# untitled.net
KiCad netlist of a schematic drawn in EAGLE
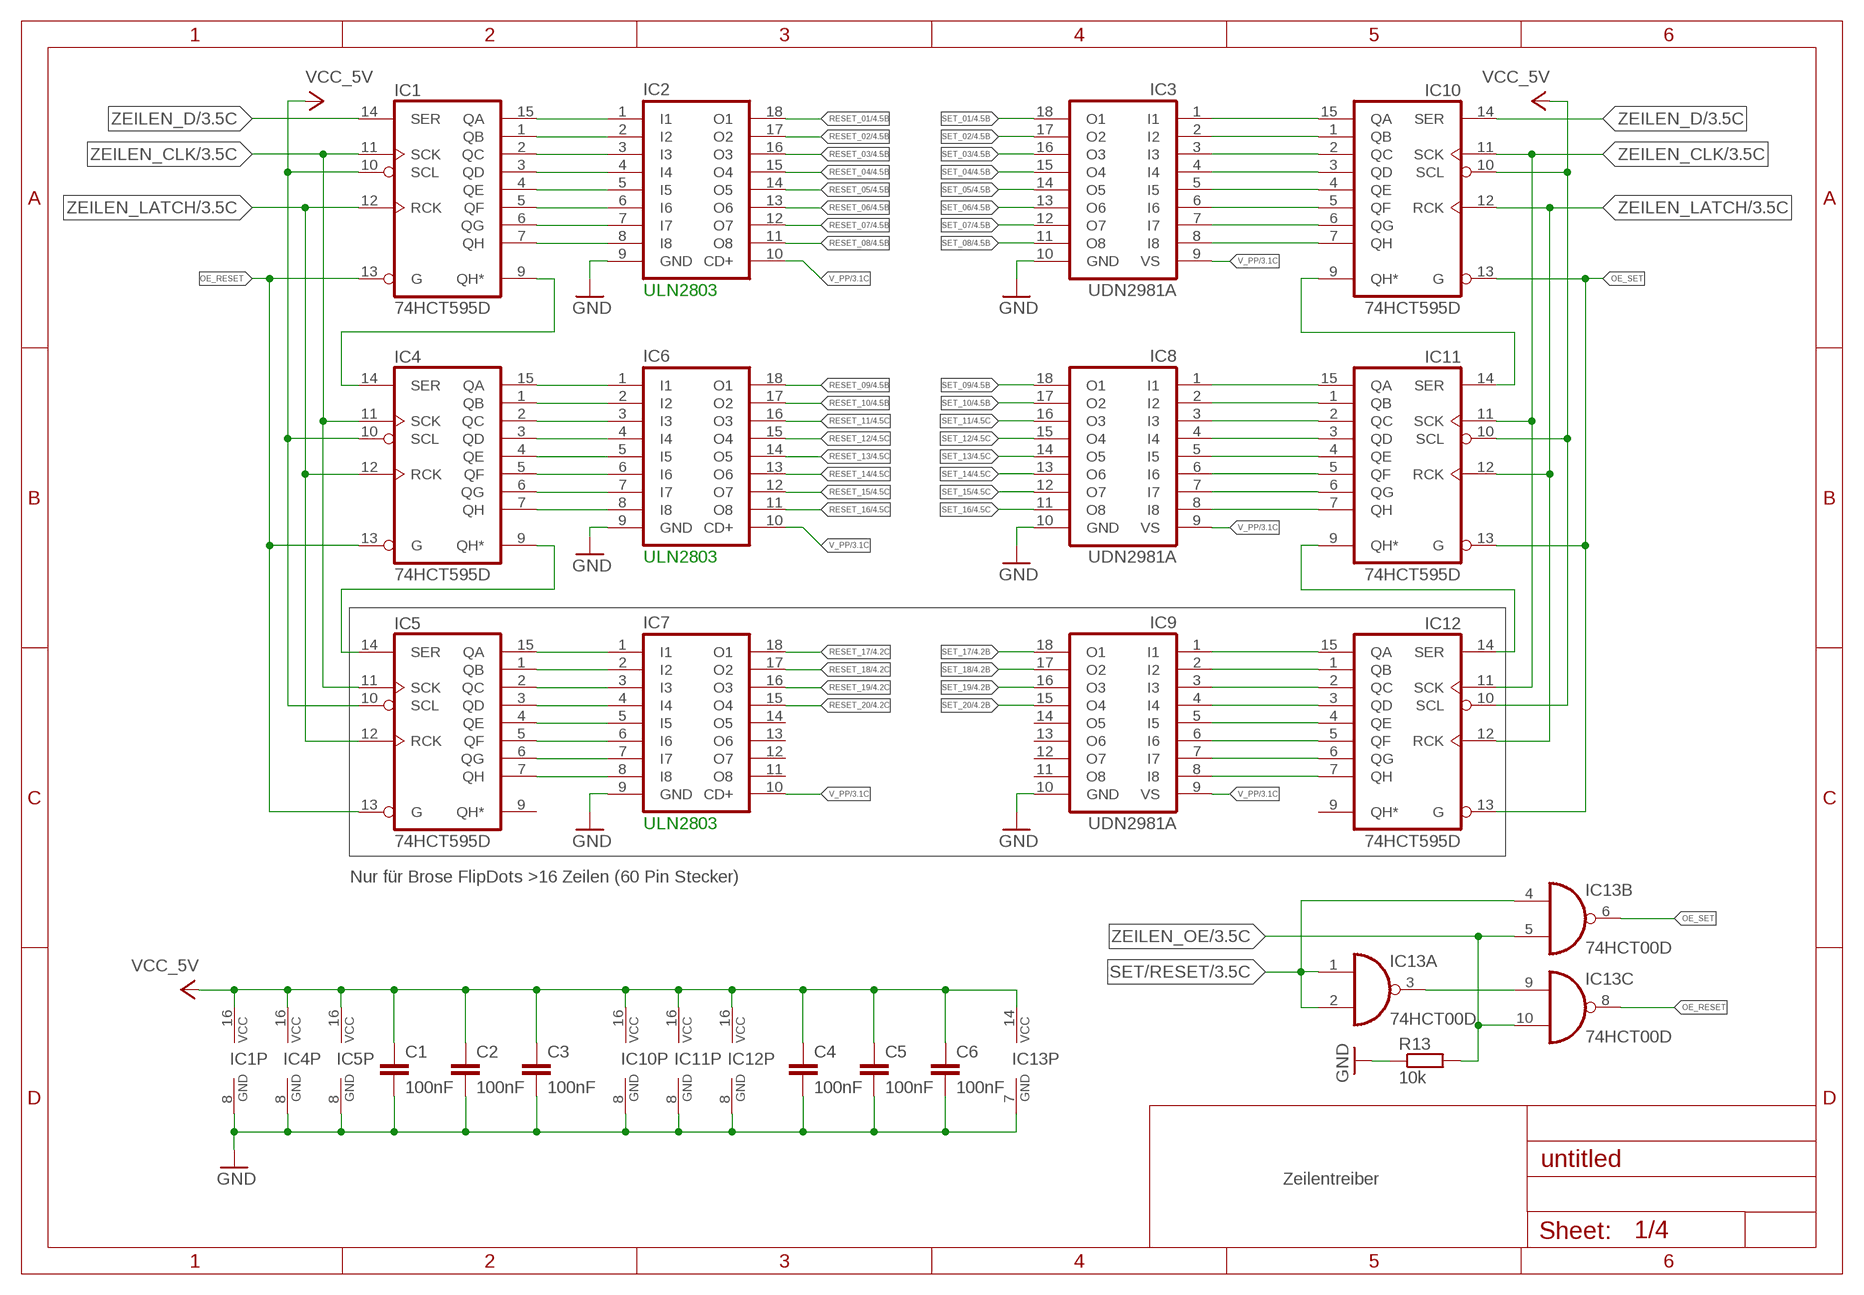
[diagram p0: schematic, sheet 1]
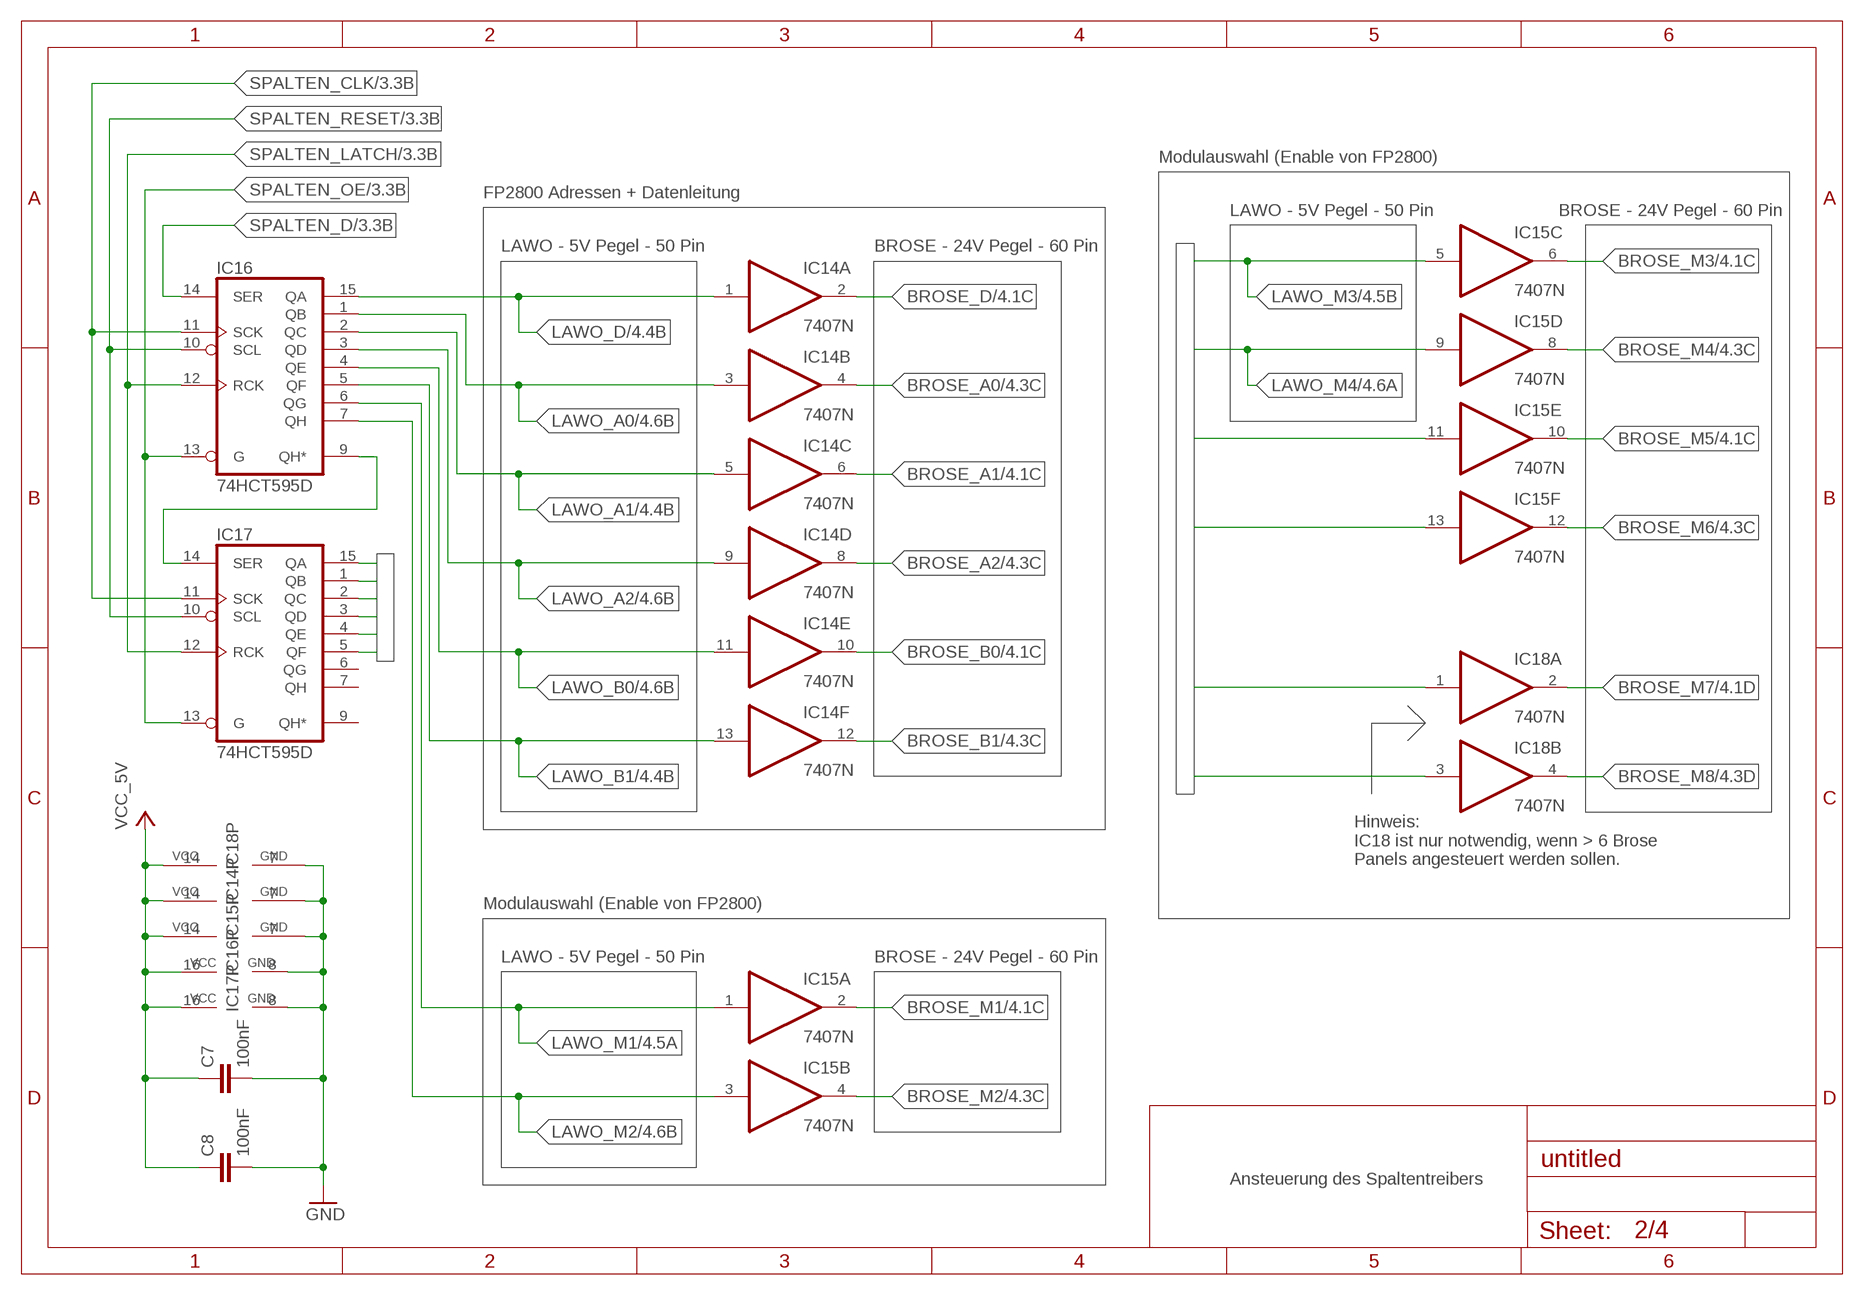
[diagram p1: schematic, sheet 2]
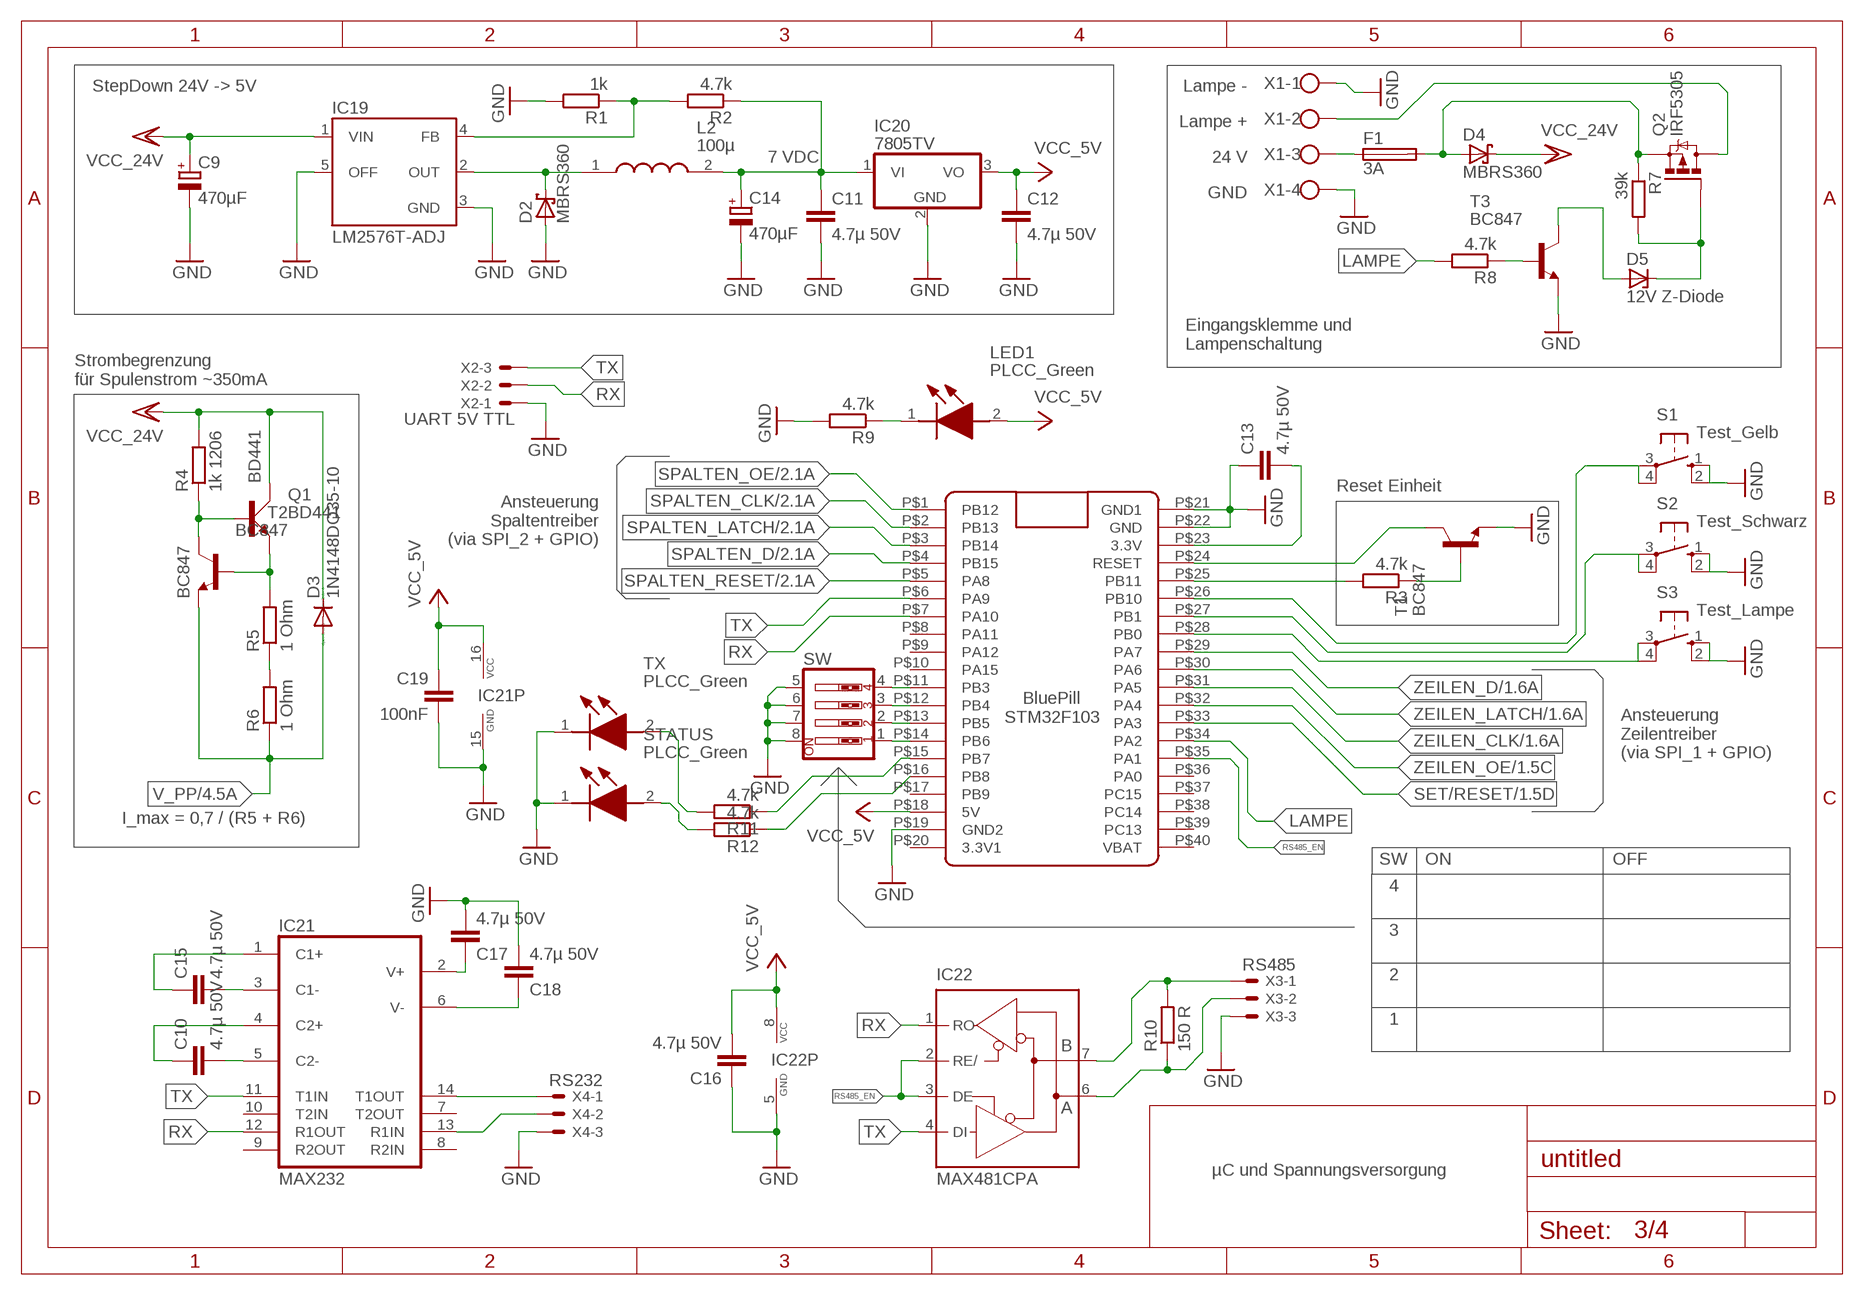
[diagram p2: schematic, sheet 3]
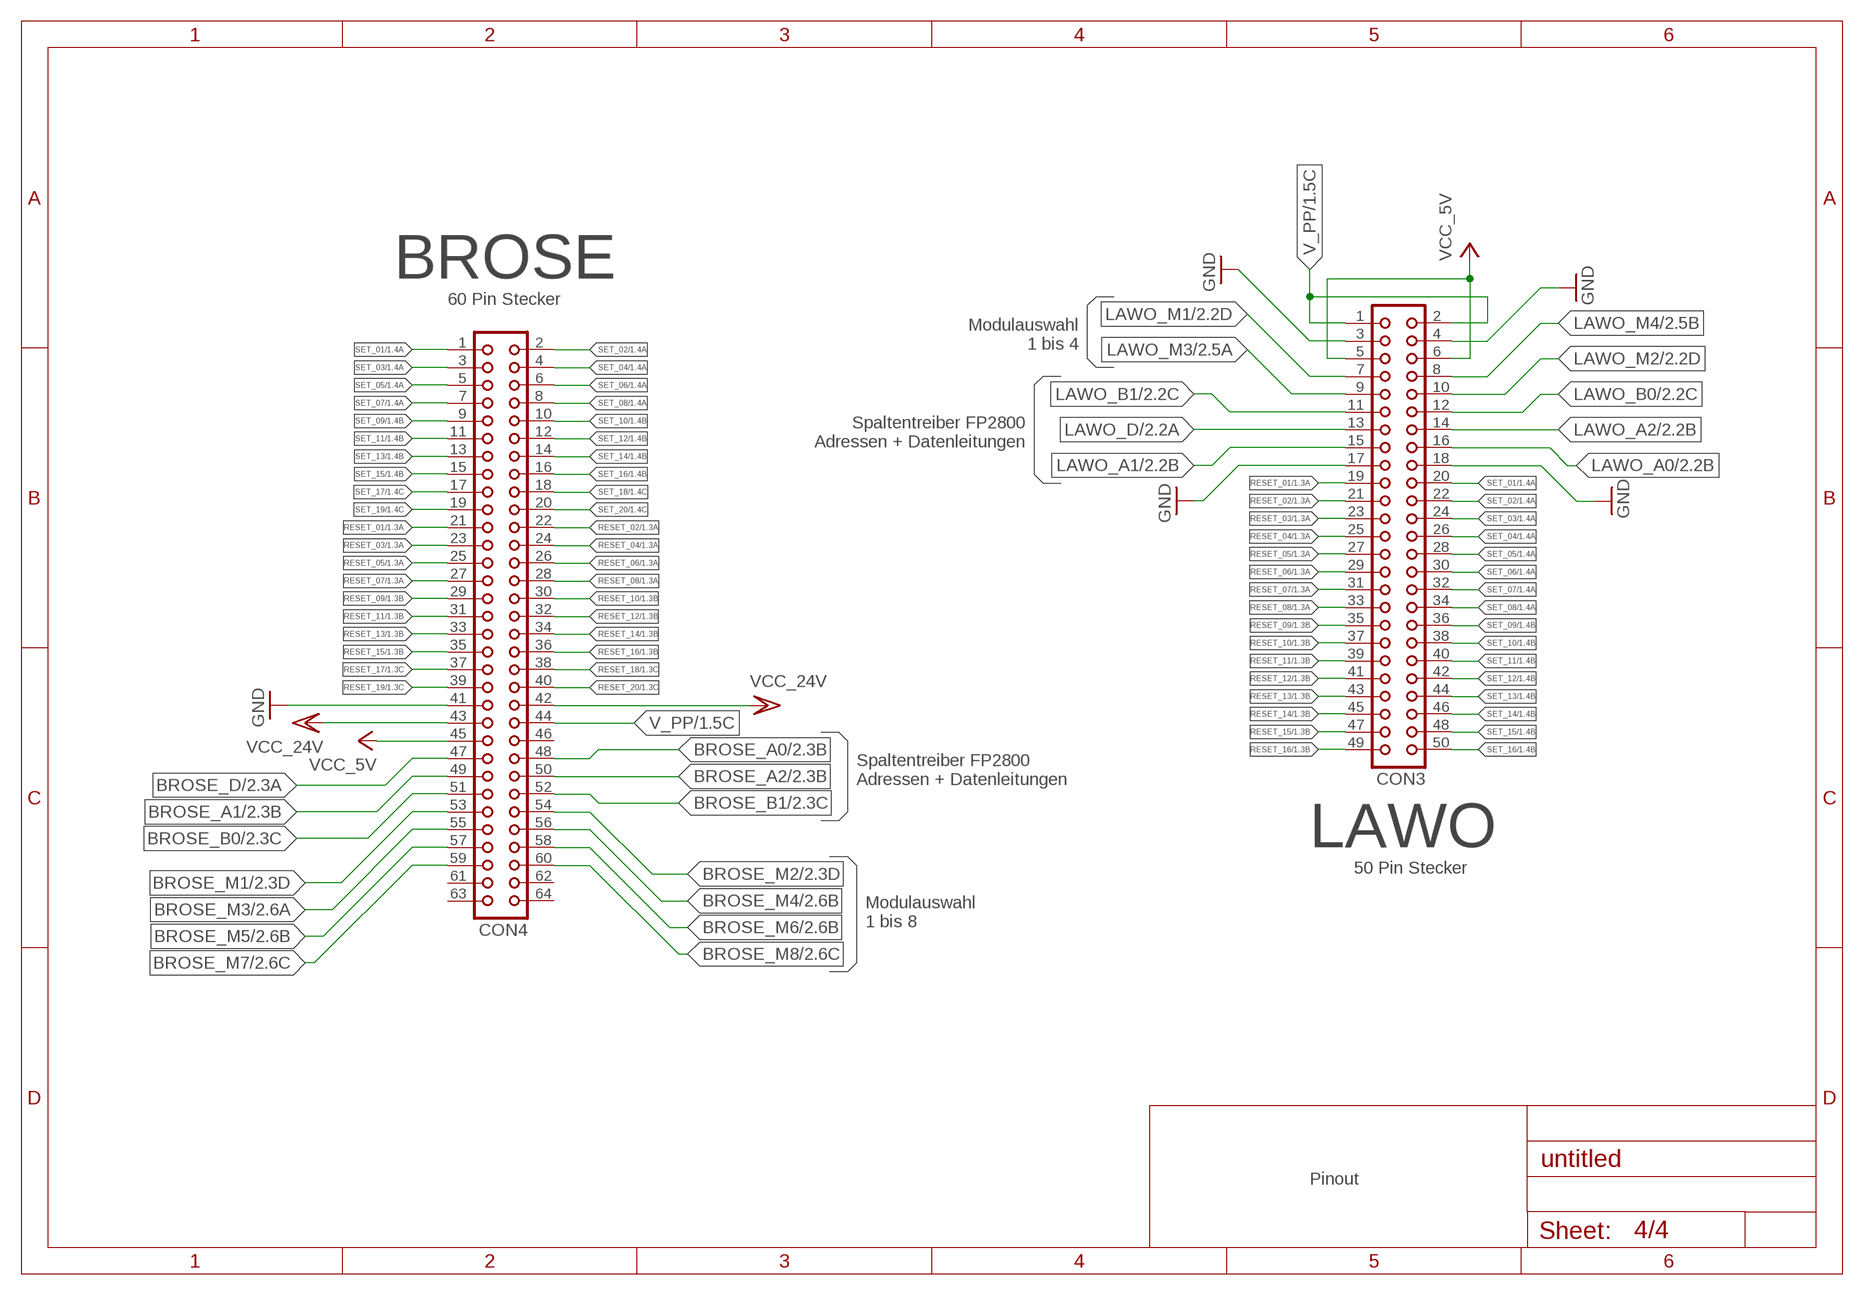
[diagram p3: schematic, sheet 4]

(export (version "E")
  (design (tool "Eeschema 10.0.6"))
  (components
    (comp (ref "C9")
      (value "470µF")
      (footprint "eagle-import:E5-10,5")
      (libsource (lib "eagle-import") (part "CPOL-EUE5-10.5"))
    )
    (comp (ref "C10")
      (value "4.7µ 50V")
      (footprint "eagle-import:C1210K")
      (libsource (lib "eagle-import") (part "C-EUC1210K"))
    )
    (comp (ref "C11")
      (value "4.7µ 50V")
      (footprint "eagle-import:C1210K")
      (libsource (lib "eagle-import") (part "C-EUC1210K"))
    )
    (comp (ref "C12")
      (value "4.7µ 50V")
      (footprint "eagle-import:C1210K")
      (libsource (lib "eagle-import") (part "C-EUC1210K"))
    )
    (comp (ref "C13")
      (value "4.7µ 50V")
      (footprint "eagle-import:C1210K")
      (libsource (lib "eagle-import") (part "C-EUC1210K"))
    )
    (comp (ref "C14")
      (value "470µF")
      (footprint "eagle-import:E5-10,5")
      (libsource (lib "eagle-import") (part "CPOL-EUE5-10.5"))
    )
    (comp (ref "C15")
      (value "4.7µ 50V")
      (footprint "eagle-import:C1210K")
      (libsource (lib "eagle-import") (part "C-EUC1210K"))
    )
    (comp (ref "C16")
      (value "4.7µ 50V")
      (footprint "eagle-import:C1210K")
      (libsource (lib "eagle-import") (part "C-EUC1210K"))
    )
    (comp (ref "C17")
      (value "4.7µ 50V")
      (footprint "eagle-import:C1210K")
      (libsource (lib "eagle-import") (part "C-EUC1210K"))
    )
    (comp (ref "C18")
      (value "4.7µ 50V")
      (footprint "eagle-import:C1210K")
      (libsource (lib "eagle-import") (part "C-EUC1210K"))
    )
    (comp (ref "C19")
      (value "100nF")
      (footprint "eagle-import:C1206K")
      (libsource (lib "eagle-import") (part "C-EUC1206K"))
    )
    (comp (ref "D2")
      (value "MBRS360")
      (footprint "eagle-import:SMC")
      (libsource (lib "eagle-import") (part "MBRS30T34"))
    )
    (comp (ref "D3")
      (value "1N4148DO35-10")
      (footprint "eagle-import:DO35-10")
      (libsource (lib "eagle-import") (part "1N4148DO35-10"))
    )
    (comp (ref "D4")
      (value "MBRS360")
      (footprint "eagle-import:SMC")
      (libsource (lib "eagle-import") (part "MBRS30T34"))
    )
    (comp (ref "D5")
      (value "12V Z-Diode")
      (footprint "eagle-import:SOD80C")
      (libsource (lib "eagle-import") (part "ZENER-DIODESOD80C"))
    )
    (comp (ref "F1")
      (value "3A")
      (footprint "eagle-import:SH22,5")
      (fields (field (name "MF") "SCHURTER") (field (name "MPN") "0031.8201"))
      (libsource (lib "eagle-import") (part "SH22,5"))
    )
    (comp (ref "IC19")
      (value "LM2576T-ADJ")
      (footprint "eagle-import:TO220-5")
      (libsource (lib "eagle-import") (part "LM2576T"))
    )
    (comp (ref "IC20")
      (value "7805TV")
      (footprint "eagle-import:TO220V")
      (libsource (lib "eagle-import") (part "78TV05"))
    )
    (comp (ref "IC21")
      (value "MAX232")
      (footprint "eagle-import:DIL16")
      (fields (field (name "MF") "MAXIM") (field (name "MPN") "MAX232ACPE+"))
      (libsource (lib "eagle-import") (part "MAX232"))
    )
    (comp (ref "IC22")
      (value "MAX481CPA")
      (footprint "eagle-import:DIL08")
      (fields (field (name "MPN") "MAX481CPA+"))
      (libsource (lib "eagle-import") (part "MAX481CPA"))
    )
    (comp (ref "L2")
      (value "100µ")
      (footprint "eagle-import:09HCP121M50")
      (fields
        (field (name "MANUFACTURER_PART_NUMBER") "09HCP-121M-50")
        (field (name "MOUSER_PART_NUMBER") "434-09HCP-121M")
      )
      (libsource (lib "eagle-import") (part "09HCP-121M-50"))
    )
    (comp (ref "LED1")
      (value "PLCC_Green")
      (footprint "eagle-import:LEDM3528X190N")
      (fields
        (field (name "MANUFACTURER_PART_NUMBER") "LTST-T680TGWT")
        (field (name "MOUSER_PART_NUMBER") "859-LTST-T680TGWT")
      )
      (libsource (lib "eagle-import") (part "LTST-T680TGWT"))
    )
    (comp (ref "Q1")
      (value "BD441")
      (footprint "eagle-import:TO126AV")
      (libsource (lib "eagle-import") (part "BD437"))
    )
    (comp (ref "Q2")
      (value "IRF5305")
      (footprint "eagle-import:TO220BV")
      (libsource (lib "eagle-import") (part "IRF9530"))
    )
    (comp (ref "R1")
      (value "1k")
      (footprint "eagle-import:R0805")
      (libsource (lib "eagle-import") (part "R-EU_R0805"))
    )
    (comp (ref "R2")
      (value "4.7k")
      (footprint "eagle-import:R0805")
      (libsource (lib "eagle-import") (part "R-EU_R0805"))
    )
    (comp (ref "R3")
      (value "4.7k")
      (footprint "eagle-import:R0805")
      (libsource (lib "eagle-import") (part "R-EU_R0805"))
    )
    (comp (ref "R4")
      (value "1k 1206")
      (footprint "eagle-import:R1206")
      (libsource (lib "eagle-import") (part "R-EU_R1206"))
    )
    (comp (ref "R5")
      (value "1 Ohm")
      (footprint "eagle-import:M1206")
      (libsource (lib "eagle-import") (part "R-EU_M1206"))
    )
    (comp (ref "R6")
      (value "1 Ohm")
      (footprint "eagle-import:M1206")
      (libsource (lib "eagle-import") (part "R-EU_M1206"))
    )
    (comp (ref "R7")
      (value "39k")
      (footprint "eagle-import:R0805")
      (libsource (lib "eagle-import") (part "R-EU_R0805"))
    )
    (comp (ref "R8")
      (value "4.7k")
      (footprint "eagle-import:R0805")
      (libsource (lib "eagle-import") (part "R-EU_R0805"))
    )
    (comp (ref "R9")
      (value "4.7k")
      (footprint "eagle-import:R0805")
      (libsource (lib "eagle-import") (part "R-EU_R0805"))
    )
    (comp (ref "R10")
      (value "150 R")
      (footprint "eagle-import:R1206")
      (libsource (lib "eagle-import") (part "R-EU_R1206"))
    )
    (comp (ref "R11")
      (value "4.7k")
      (footprint "eagle-import:R0805")
      (libsource (lib "eagle-import") (part "R-EU_R0805"))
    )
    (comp (ref "R12")
      (value "4.7k")
      (footprint "eagle-import:R0805")
      (libsource (lib "eagle-import") (part "R-EU_R0805"))
    )
    (comp (ref "S1")
      (value "Test_Gelb")
      (footprint "eagle-import:B3F-10XX")
      (fields (field (name "MPN") "B3F-1000"))
      (libsource (lib "eagle-import") (part "10-XX"))
    )
    (comp (ref "S2")
      (value "Test_Schwarz")
      (footprint "eagle-import:B3F-10XX")
      (fields (field (name "MPN") "B3F-1000"))
      (libsource (lib "eagle-import") (part "10-XX"))
    )
    (comp (ref "S3")
      (value "Test_Lampe")
      (footprint "eagle-import:B3F-10XX")
      (fields (field (name "MPN") "B3F-1000"))
      (libsource (lib "eagle-import") (part "10-XX"))
    )
    (comp (ref "STATUS")
      (value "PLCC_Green")
      (footprint "eagle-import:LEDM3528X190N")
      (fields
        (field (name "MANUFACTURER_PART_NUMBER") "LTST-T680TGWT")
        (field (name "MOUSER_PART_NUMBER") "859-LTST-T680TGWT")
      )
      (libsource (lib "eagle-import") (part "LTST-T680TGWT"))
    )
    (comp (ref "SW")
      (value "SW_DIP-4")
      (footprint "eagle-import:EDG-04")
      (libsource (lib "eagle-import") (part "SW_DIP-4"))
    )
    (comp (ref "T1")
      (value "BC847")
      (footprint "eagle-import:SOT23")
      (libsource (lib "eagle-import") (part "BC847"))
    )
    (comp (ref "T2")
      (value "BC847")
      (footprint "eagle-import:SOT23")
      (libsource (lib "eagle-import") (part "BC847"))
    )
    (comp (ref "T3")
      (value "BC847")
      (footprint "eagle-import:SOT23")
      (libsource (lib "eagle-import") (part "BC847"))
    )
    (comp (ref "TX")
      (value "PLCC_Green")
      (footprint "eagle-import:LEDM3528X190N")
      (fields
        (field (name "MANUFACTURER_PART_NUMBER") "LTST-T680TGWT")
        (field (name "MOUSER_PART_NUMBER") "859-LTST-T680TGWT")
      )
      (libsource (lib "eagle-import") (part "LTST-T680TGWT"))
    )
    (comp (ref "U$1")
      (value "BLUE_PILL")
      (footprint "eagle-import:BLUE_PILL")
      (libsource (lib "eagle-import") (part "BLUE_PILL"))
    )
    (comp (ref "X1")
      (value "W237-4")
      (footprint "eagle-import:W237-4")
      (libsource (lib "eagle-import") (part "W237-4"))
    )
    (comp (ref "X2")
      (value "UART 5V TTL")
      (footprint "eagle-import:22-23-2031")
      (fields (field (name "MF") "MOLEX") (field (name "MPN") "22-23-2031"))
      (libsource (lib "eagle-import") (part "22-23-2031"))
    )
    (comp (ref "X3")
      (value "RS485")
      (footprint "eagle-import:22-23-2031")
      (fields (field (name "MF") "MOLEX") (field (name "MPN") "22-23-2031"))
      (libsource (lib "eagle-import") (part "22-23-2031"))
    )
    (comp (ref "X4")
      (value "RS232")
      (footprint "eagle-import:22-23-2031")
      (fields (field (name "MF") "MOLEX") (field (name "MPN") "22-23-2031"))
      (libsource (lib "eagle-import") (part "22-23-2031"))
    )
    (comp (ref "CON3")
      (value "CON50")
      (footprint "eagle-import:CON50")
      (libsource (lib "eagle-import") (part "CON50"))
    )
    (comp (ref "CON4")
      (value "CON64")
      (footprint "eagle-import:CON64")
      (libsource (lib "eagle-import") (part "CON64"))
    )
    (comp (ref "C7")
      (value "100nF")
      (footprint "eagle-import:C1206K")
      (libsource (lib "eagle-import") (part "resistor_C-EUC1206K"))
    )
    (comp (ref "C8")
      (value "100nF")
      (footprint "eagle-import:C1206K")
      (libsource (lib "eagle-import") (part "resistor_C-EUC1206K"))
    )
    (comp (ref "IC14")
      (value "7407N")
      (footprint "eagle-import:DIL14")
      (libsource (lib "eagle-import") (part "7407N"))
    )
    (comp (ref "IC15")
      (value "7407N")
      (footprint "eagle-import:DIL14")
      (libsource (lib "eagle-import") (part "7407N"))
    )
    (comp (ref "IC16")
      (value "74HCT595D")
      (footprint "eagle-import:SO16")
      (libsource (lib "eagle-import") (part "74595DHCT"))
    )
    (comp (ref "IC17")
      (value "74HCT595D")
      (footprint "eagle-import:SO16")
      (libsource (lib "eagle-import") (part "74595DHCT"))
    )
    (comp (ref "IC18")
      (value "7407N")
      (footprint "eagle-import:DIL14")
      (libsource (lib "eagle-import") (part "7407N"))
    )
    (comp (ref "C1")
      (value "100nF")
      (footprint "eagle-import:C1206K")
      (libsource (lib "eagle-import") (part "C-EUC1206K"))
    )
    (comp (ref "C2")
      (value "100nF")
      (footprint "eagle-import:C1206K")
      (libsource (lib "eagle-import") (part "C-EUC1206K"))
    )
    (comp (ref "C3")
      (value "100nF")
      (footprint "eagle-import:C1206K")
      (libsource (lib "eagle-import") (part "C-EUC1206K"))
    )
    (comp (ref "C4")
      (value "100nF")
      (footprint "eagle-import:C1206K")
      (libsource (lib "eagle-import") (part "C-EUC1206K"))
    )
    (comp (ref "C5")
      (value "100nF")
      (footprint "eagle-import:C1206K")
      (libsource (lib "eagle-import") (part "C-EUC1206K"))
    )
    (comp (ref "C6")
      (value "100nF")
      (footprint "eagle-import:C1206K")
      (libsource (lib "eagle-import") (part "C-EUC1206K"))
    )
    (comp (ref "IC1")
      (value "74HCT595D")
      (footprint "eagle-import:SO16")
      (libsource (lib "eagle-import") (part "74595DHCT"))
    )
    (comp (ref "IC2")
      (value "ULN2803A")
      (footprint "eagle-import:DIL18")
      (libsource (lib "eagle-import") (part "ULN2803A"))
    )
    (comp (ref "IC3")
      (value "UDN2981A")
      (footprint "eagle-import:DIL18")
      (libsource (lib "eagle-import") (part "UDN298A1"))
    )
    (comp (ref "IC4")
      (value "74HCT595D")
      (footprint "eagle-import:SO16")
      (libsource (lib "eagle-import") (part "74595DHCT"))
    )
    (comp (ref "IC5")
      (value "74HCT595D")
      (footprint "eagle-import:SO16")
      (libsource (lib "eagle-import") (part "74595DHCT"))
    )
    (comp (ref "IC6")
      (value "ULN2803A")
      (footprint "eagle-import:DIL18")
      (libsource (lib "eagle-import") (part "ULN2803A"))
    )
    (comp (ref "IC7")
      (value "ULN2803A")
      (footprint "eagle-import:DIL18")
      (libsource (lib "eagle-import") (part "ULN2803A"))
    )
    (comp (ref "IC8")
      (value "UDN2981A")
      (footprint "eagle-import:DIL18")
      (libsource (lib "eagle-import") (part "UDN298A1"))
    )
    (comp (ref "IC9")
      (value "UDN2981A")
      (footprint "eagle-import:DIL18")
      (libsource (lib "eagle-import") (part "UDN298A1"))
    )
    (comp (ref "IC10")
      (value "74HCT595D")
      (footprint "eagle-import:SO16")
      (libsource (lib "eagle-import") (part "74595DHCT"))
    )
    (comp (ref "IC11")
      (value "74HCT595D")
      (footprint "eagle-import:SO16")
      (libsource (lib "eagle-import") (part "74595DHCT"))
    )
    (comp (ref "IC12")
      (value "74HCT595D")
      (footprint "eagle-import:SO16")
      (libsource (lib "eagle-import") (part "74595DHCT"))
    )
    (comp (ref "IC13")
      (value "74HCT00D")
      (footprint "eagle-import:SO14")
      (libsource (lib "eagle-import") (part "7400DHCT"))
    )
    (comp (ref "R13")
      (value "10k")
      (footprint "eagle-import:R0805")
      (libsource (lib "eagle-import") (part "R-EU_R0805"))
    )
  )
  (nets
    (net (code "1") (name "BROSE_A0") (class "Default")
      (node (ref "CON4") (pin "48") (pinfunction "48_48") (pintype "passive"))
      (node (ref "IC14") (pin "4") (pinfunction "O_4") (pintype "open_collector"))
    )
    (net (code "2") (name "BROSE_A1") (class "Default")
      (node (ref "CON4") (pin "49") (pinfunction "49_49") (pintype "passive"))
      (node (ref "IC14") (pin "6") (pinfunction "O_6") (pintype "open_collector"))
    )
    (net (code "3") (name "BROSE_A2") (class "Default")
      (node (ref "CON4") (pin "50") (pinfunction "50_50") (pintype "passive"))
      (node (ref "IC14") (pin "8") (pinfunction "O_8") (pintype "open_collector"))
    )
    (net (code "4") (name "BROSE_B0") (class "Default")
      (node (ref "CON4") (pin "51") (pinfunction "51_51") (pintype "passive"))
      (node (ref "IC14") (pin "10") (pinfunction "O_10") (pintype "open_collector"))
    )
    (net (code "5") (name "BROSE_B1") (class "Default")
      (node (ref "CON4") (pin "52") (pinfunction "52_52") (pintype "passive"))
      (node (ref "IC14") (pin "12") (pinfunction "O_12") (pintype "open_collector"))
    )
    (net (code "6") (name "BROSE_D") (class "Default")
      (node (ref "CON4") (pin "47") (pinfunction "47_47") (pintype "passive"))
      (node (ref "IC14") (pin "2") (pinfunction "O_2") (pintype "open_collector"))
    )
    (net (code "7") (name "BROSE_M1") (class "Default")
      (node (ref "CON4") (pin "53") (pinfunction "53_53") (pintype "passive"))
      (node (ref "IC15") (pin "2") (pinfunction "O_2") (pintype "open_collector"))
    )
    (net (code "8") (name "BROSE_M2") (class "Default")
      (node (ref "CON4") (pin "54") (pinfunction "54_54") (pintype "passive"))
      (node (ref "IC15") (pin "4") (pinfunction "O_4") (pintype "open_collector"))
    )
    (net (code "9") (name "BROSE_M3") (class "Default")
      (node (ref "CON4") (pin "55") (pinfunction "55_55") (pintype "passive"))
      (node (ref "IC15") (pin "6") (pinfunction "O_6") (pintype "open_collector"))
    )
    (net (code "10") (name "BROSE_M4") (class "Default")
      (node (ref "CON4") (pin "56") (pinfunction "56_56") (pintype "passive"))
      (node (ref "IC15") (pin "8") (pinfunction "O_8") (pintype "open_collector"))
    )
    (net (code "11") (name "BROSE_M5") (class "Default")
      (node (ref "CON4") (pin "57") (pinfunction "57_57") (pintype "passive"))
      (node (ref "IC15") (pin "10") (pinfunction "O_10") (pintype "open_collector"))
    )
    (net (code "12") (name "BROSE_M6") (class "Default")
      (node (ref "CON4") (pin "58") (pinfunction "58_58") (pintype "passive"))
      (node (ref "IC15") (pin "12") (pinfunction "O_12") (pintype "open_collector"))
    )
    (net (code "13") (name "BROSE_M7") (class "Default")
      (node (ref "CON4") (pin "59") (pinfunction "59_59") (pintype "passive"))
      (node (ref "IC18") (pin "2") (pinfunction "O_2") (pintype "open_collector"))
    )
    (net (code "14") (name "BROSE_M8") (class "Default")
      (node (ref "CON4") (pin "60") (pinfunction "60_60") (pintype "passive"))
      (node (ref "IC18") (pin "4") (pinfunction "O_4") (pintype "open_collector"))
    )
    (net (code "15") (name "GND") (class "Default")
      (node (ref "C1") (pin "2") (pinfunction "2_2") (pintype "passive"))
      (node (ref "C11") (pin "2") (pinfunction "2_2") (pintype "passive"))
      (node (ref "C12") (pin "2") (pinfunction "2_2") (pintype "passive"))
      (node (ref "C13") (pin "1") (pinfunction "1_1") (pintype "passive"))
      (node (ref "C14") (pin "-") (pinfunction "-_-") (pintype "passive"))
      (node (ref "C16") (pin "1") (pinfunction "1_1") (pintype "passive"))
      (node (ref "C17") (pin "2") (pinfunction "2_2") (pintype "passive"))
      (node (ref "C18") (pin "2") (pinfunction "2_2") (pintype "passive"))
      (node (ref "C19") (pin "2") (pinfunction "2_2") (pintype "passive"))
      (node (ref "C2") (pin "2") (pinfunction "2_2") (pintype "passive"))
      (node (ref "C3") (pin "2") (pinfunction "2_2") (pintype "passive"))
      (node (ref "C4") (pin "2") (pinfunction "2_2") (pintype "passive"))
      (node (ref "C5") (pin "2") (pinfunction "2_2") (pintype "passive"))
      (node (ref "C6") (pin "2") (pinfunction "2_2") (pintype "passive"))
      (node (ref "C7") (pin "2") (pinfunction "2_2") (pintype "passive"))
      (node (ref "C8") (pin "2") (pinfunction "2_2") (pintype "passive"))
      (node (ref "C9") (pin "-") (pinfunction "-_-") (pintype "passive"))
      (node (ref "CON3") (pin "17") (pinfunction "17_17") (pintype "passive"))
      (node (ref "CON3") (pin "18") (pinfunction "18_18") (pintype "passive"))
      (node (ref "CON3") (pin "3") (pinfunction "3_3") (pintype "passive"))
      (node (ref "CON3") (pin "4") (pinfunction "4_4") (pintype "passive"))
      (node (ref "CON4") (pin "41") (pinfunction "41_41") (pintype "passive"))
      (node (ref "D2") (pin "A") (pinfunction "A_A") (pintype "passive"))
      (node (ref "IC1") (pin "8") (pinfunction "GND_8") (pintype "power_in"))
      (node (ref "IC10") (pin "8") (pinfunction "GND_8") (pintype "power_in"))
      (node (ref "IC11") (pin "8") (pinfunction "GND_8") (pintype "power_in"))
      (node (ref "IC12") (pin "8") (pinfunction "GND_8") (pintype "power_in"))
      (node (ref "IC13") (pin "7") (pinfunction "GND_7") (pintype "power_in"))
      (node (ref "IC14") (pin "7") (pinfunction "GND_7") (pintype "power_in"))
      (node (ref "IC15") (pin "7") (pinfunction "GND_7") (pintype "power_in"))
      (node (ref "IC16") (pin "8") (pinfunction "GND_8") (pintype "power_in"))
      (node (ref "IC17") (pin "8") (pinfunction "GND_8") (pintype "power_in"))
      (node (ref "IC18") (pin "7") (pinfunction "GND_7") (pintype "power_in"))
      (node (ref "IC19") (pin "3") (pinfunction "GND_3") (pintype "power_in"))
      (node (ref "IC19") (pin "5") (pinfunction "OFF_5") (pintype "input"))
      (node (ref "IC2") (pin "9") (pinfunction "GND_9") (pintype "power_in"))
      (node (ref "IC20") (pin "2") (pinfunction "GND_2") (pintype "passive"))
      (node (ref "IC21") (pin "15") (pinfunction "GND_15") (pintype "power_in"))
      (node (ref "IC22") (pin "5") (pinfunction "GND_5") (pintype "power_in"))
      (node (ref "IC3") (pin "10") (pinfunction "GND_10") (pintype "power_in"))
      (node (ref "IC4") (pin "8") (pinfunction "GND_8") (pintype "power_in"))
      (node (ref "IC5") (pin "8") (pinfunction "GND_8") (pintype "power_in"))
      (node (ref "IC6") (pin "9") (pinfunction "GND_9") (pintype "power_in"))
      (node (ref "IC7") (pin "9") (pinfunction "GND_9") (pintype "power_in"))
      (node (ref "IC8") (pin "10") (pinfunction "GND_10") (pintype "power_in"))
      (node (ref "IC9") (pin "10") (pinfunction "GND_10") (pintype "power_in"))
      (node (ref "R1") (pin "2") (pinfunction "2_2") (pintype "passive"))
      (node (ref "R13") (pin "1") (pinfunction "1_1") (pintype "passive"))
      (node (ref "R9") (pin "2") (pinfunction "2_2") (pintype "passive"))
      (node (ref "S1") (pin "1") (pinfunction "S_1") (pintype "passive"))
      (node (ref "S1") (pin "2") (pinfunction "S1_2") (pintype "passive"))
      (node (ref "S2") (pin "1") (pinfunction "S_1") (pintype "passive"))
      (node (ref "S2") (pin "2") (pinfunction "S1_2") (pintype "passive"))
      (node (ref "S3") (pin "1") (pinfunction "S_1") (pintype "passive"))
      (node (ref "S3") (pin "2") (pinfunction "S1_2") (pintype "passive"))
      (node (ref "STATUS") (pin "1") (pinfunction "K_1") (pintype "bidirectional"))
      (node (ref "SW") (pin "5") (pinfunction "5_5") (pintype "passive"))
      (node (ref "SW") (pin "6") (pinfunction "6_6") (pintype "passive"))
      (node (ref "SW") (pin "7") (pinfunction "7_7") (pintype "passive"))
      (node (ref "SW") (pin "8") (pinfunction "8_8") (pintype "passive"))
      (node (ref "T1") (pin "2") (pinfunction "E_2") (pintype "passive"))
      (node (ref "T3") (pin "2") (pinfunction "E_2") (pintype "passive"))
      (node (ref "TX") (pin "1") (pinfunction "K_1") (pintype "bidirectional"))
      (node (ref "U$1") (pin "P$19") (pinfunction "GND2_P$19") (pintype "bidirectional"))
      (node (ref "U$1") (pin "P$21") (pinfunction "GND1_P$21") (pintype "power_in"))
      (node (ref "U$1") (pin "P$22") (pinfunction "GND_P$22") (pintype "bidirectional"))
      (node (ref "X1") (pin "1") (pinfunction "KL_1") (pintype "passive"))
      (node (ref "X1") (pin "4") (pinfunction "KL_4") (pintype "passive"))
      (node (ref "X2") (pin "1") (pinfunction "S_1") (pintype "passive"))
      (node (ref "X3") (pin "3") (pinfunction "S_3") (pintype "passive"))
      (node (ref "X4") (pin "3") (pinfunction "S_3") (pintype "passive"))
    )
    (net (code "16") (name "LAMPE") (class "Default")
      (node (ref "R8") (pin "2") (pinfunction "2_2") (pintype "passive"))
      (node (ref "U$1") (pin "P$34") (pinfunction "PA2_P$34") (pintype "bidirectional"))
    )
    (net (code "17") (name "LAWO_A0") (class "Default")
      (node (ref "CON3") (pin "16") (pinfunction "16_16") (pintype "passive"))
      (node (ref "IC14") (pin "3") (pinfunction "I_3") (pintype "input"))
      (node (ref "IC16") (pin "1") (pinfunction "QB_1") (pintype "tri_state"))
    )
    (net (code "18") (name "LAWO_A1") (class "Default")
      (node (ref "CON3") (pin "15") (pinfunction "15_15") (pintype "passive"))
      (node (ref "IC14") (pin "5") (pinfunction "I_5") (pintype "input"))
      (node (ref "IC16") (pin "2") (pinfunction "QC_2") (pintype "tri_state"))
    )
    (net (code "19") (name "LAWO_A2") (class "Default")
      (node (ref "CON3") (pin "14") (pinfunction "14_14") (pintype "passive"))
      (node (ref "IC14") (pin "9") (pinfunction "I_9") (pintype "input"))
      (node (ref "IC16") (pin "3") (pinfunction "QD_3") (pintype "tri_state"))
    )
    (net (code "20") (name "LAWO_B0") (class "Default")
      (node (ref "CON3") (pin "12") (pinfunction "12_12") (pintype "passive"))
      (node (ref "IC14") (pin "11") (pinfunction "I_11") (pintype "input"))
      (node (ref "IC16") (pin "4") (pinfunction "QE_4") (pintype "tri_state"))
    )
    (net (code "21") (name "LAWO_B1") (class "Default")
      (node (ref "CON3") (pin "11") (pinfunction "11_11") (pintype "passive"))
      (node (ref "IC14") (pin "13") (pinfunction "I_13") (pintype "input"))
      (node (ref "IC16") (pin "5") (pinfunction "QF_5") (pintype "tri_state"))
    )
    (net (code "22") (name "LAWO_D") (class "Default")
      (node (ref "CON3") (pin "13") (pinfunction "13_13") (pintype "passive"))
      (node (ref "IC14") (pin "1") (pinfunction "I_1") (pintype "input"))
      (node (ref "IC16") (pin "15") (pinfunction "QA_15") (pintype "tri_state"))
    )
    (net (code "23") (name "LAWO_M1") (class "Default")
      (node (ref "CON3") (pin "7") (pinfunction "7_7") (pintype "passive"))
      (node (ref "IC15") (pin "1") (pinfunction "I_1") (pintype "input"))
      (node (ref "IC16") (pin "6") (pinfunction "QG_6") (pintype "tri_state"))
    )
    (net (code "24") (name "LAWO_M2") (class "Default")
      (node (ref "CON3") (pin "10") (pinfunction "10_10") (pintype "passive"))
      (node (ref "IC15") (pin "3") (pinfunction "I_3") (pintype "input"))
      (node (ref "IC16") (pin "7") (pinfunction "QH_7") (pintype "tri_state"))
    )
    (net (code "25") (name "LAWO_M3") (class "Default")
      (node (ref "CON3") (pin "9") (pinfunction "9_9") (pintype "passive"))
      (node (ref "IC15") (pin "5") (pinfunction "I_5") (pintype "input"))
      (node (ref "IC17") (pin "15") (pinfunction "QA_15") (pintype "tri_state"))
    )
    (net (code "26") (name "LAWO_M4") (class "Default")
      (node (ref "CON3") (pin "8") (pinfunction "8_8") (pintype "passive"))
      (node (ref "IC15") (pin "9") (pinfunction "I_9") (pintype "input"))
      (node (ref "IC17") (pin "1") (pinfunction "QB_1") (pintype "tri_state"))
    )
    (net (code "27") (name "LAWO_M5") (class "Default")
      (node (ref "IC15") (pin "11") (pinfunction "I_11") (pintype "input"))
      (node (ref "IC17") (pin "2") (pinfunction "QC_2") (pintype "tri_state"))
    )
    (net (code "28") (name "LAWO_M6") (class "Default")
      (node (ref "IC15") (pin "13") (pinfunction "I_13") (pintype "input"))
      (node (ref "IC17") (pin "3") (pinfunction "QD_3") (pintype "tri_state"))
    )
    (net (code "29") (name "LAWO_M7") (class "Default")
      (node (ref "IC17") (pin "4") (pinfunction "QE_4") (pintype "tri_state"))
      (node (ref "IC18") (pin "1") (pinfunction "I_1") (pintype "input"))
    )
    (net (code "30") (name "LAWO_M8") (class "Default")
      (node (ref "IC17") (pin "5") (pinfunction "QF_5") (pintype "tri_state"))
      (node (ref "IC18") (pin "3") (pinfunction "I_3") (pintype "input"))
    )
    (net (code "31") (name "Net-(D4-PadA)") (class "Default")
      (node (ref "D4") (pin "A") (pinfunction "A_A") (pintype "passive"))
      (node (ref "F1") (pin "2") (pinfunction "2_2") (pintype "passive"))
      (node (ref "Q2") (pin "S") (pinfunction "S_S") (pintype "passive"))
      (node (ref "R7") (pin "1") (pinfunction "1_1") (pintype "passive"))
    )
    (net (code "32") (name "Net-(D5-PadC)") (class "Default")
      (node (ref "D5") (pin "C") (pinfunction "C_C") (pintype "passive"))
      (node (ref "Q2") (pin "G") (pinfunction "G_G") (pintype "passive"))
      (node (ref "R7") (pin "2") (pinfunction "2_2") (pintype "passive"))
    )
    (net (code "33") (name "Net-(IC1A-QA)") (class "Default")
      (node (ref "IC1") (pin "15") (pinfunction "QA_15") (pintype "tri_state"))
      (node (ref "IC2") (pin "1") (pinfunction "I1_1") (pintype "input"))
    )
    (net (code "34") (name "Net-(IC1A-QB)") (class "Default")
      (node (ref "IC1") (pin "1") (pinfunction "QB_1") (pintype "tri_state"))
      (node (ref "IC2") (pin "2") (pinfunction "I2_2") (pintype "input"))
    )
    (net (code "35") (name "Net-(IC1A-QC)") (class "Default")
      (node (ref "IC1") (pin "2") (pinfunction "QC_2") (pintype "tri_state"))
      (node (ref "IC2") (pin "3") (pinfunction "I3_3") (pintype "input"))
    )
    (net (code "36") (name "Net-(IC1A-QD)") (class "Default")
      (node (ref "IC1") (pin "3") (pinfunction "QD_3") (pintype "tri_state"))
      (node (ref "IC2") (pin "4") (pinfunction "I4_4") (pintype "input"))
    )
    (net (code "37") (name "Net-(IC1A-QE)") (class "Default")
      (node (ref "IC1") (pin "4") (pinfunction "QE_4") (pintype "tri_state"))
      (node (ref "IC2") (pin "5") (pinfunction "I5_5") (pintype "input"))
    )
    (net (code "38") (name "Net-(IC1A-QF)") (class "Default")
      (node (ref "IC1") (pin "5") (pinfunction "QF_5") (pintype "tri_state"))
      (node (ref "IC2") (pin "6") (pinfunction "I6_6") (pintype "input"))
    )
    (net (code "39") (name "Net-(IC1A-QG)") (class "Default")
      (node (ref "IC1") (pin "6") (pinfunction "QG_6") (pintype "tri_state"))
      (node (ref "IC2") (pin "7") (pinfunction "I7_7") (pintype "input"))
    )
    (net (code "40") (name "Net-(IC1A-QH)") (class "Default")
      (node (ref "IC1") (pin "7") (pinfunction "QH_7") (pintype "tri_state"))
      (node (ref "IC2") (pin "8") (pinfunction "I8_8") (pintype "input"))
    )
    (net (code "41") (name "Net-(IC1A-QH*)") (class "Default")
      (node (ref "IC1") (pin "9") (pinfunction "QH*_9") (pintype "tri_state"))
      (node (ref "IC4") (pin "14") (pinfunction "SER_14") (pintype "input"))
    )
    (net (code "42") (name "Net-(IC4A-QA)") (class "Default")
      (node (ref "IC4") (pin "15") (pinfunction "QA_15") (pintype "tri_state"))
      (node (ref "IC6") (pin "1") (pinfunction "I1_1") (pintype "input"))
    )
    (net (code "43") (name "Net-(IC4A-QB)") (class "Default")
      (node (ref "IC4") (pin "1") (pinfunction "QB_1") (pintype "tri_state"))
      (node (ref "IC6") (pin "2") (pinfunction "I2_2") (pintype "input"))
    )
    (net (code "44") (name "Net-(IC4A-QC)") (class "Default")
      (node (ref "IC4") (pin "2") (pinfunction "QC_2") (pintype "tri_state"))
      (node (ref "IC6") (pin "3") (pinfunction "I3_3") (pintype "input"))
    )
    (net (code "45") (name "Net-(IC4A-QD)") (class "Default")
      (node (ref "IC4") (pin "3") (pinfunction "QD_3") (pintype "tri_state"))
      (node (ref "IC6") (pin "4") (pinfunction "I4_4") (pintype "input"))
    )
    (net (code "46") (name "Net-(IC4A-QE)") (class "Default")
      (node (ref "IC4") (pin "4") (pinfunction "QE_4") (pintype "tri_state"))
      (node (ref "IC6") (pin "5") (pinfunction "I5_5") (pintype "input"))
    )
    (net (code "47") (name "Net-(IC4A-QF)") (class "Default")
      (node (ref "IC4") (pin "5") (pinfunction "QF_5") (pintype "tri_state"))
      (node (ref "IC6") (pin "6") (pinfunction "I6_6") (pintype "input"))
    )
    (net (code "48") (name "Net-(IC4A-QG)") (class "Default")
      (node (ref "IC4") (pin "6") (pinfunction "QG_6") (pintype "tri_state"))
      (node (ref "IC6") (pin "7") (pinfunction "I7_7") (pintype "input"))
    )
    (net (code "49") (name "Net-(IC4A-QH)") (class "Default")
      (node (ref "IC4") (pin "7") (pinfunction "QH_7") (pintype "tri_state"))
      (node (ref "IC6") (pin "8") (pinfunction "I8_8") (pintype "input"))
    )
    (net (code "50") (name "Net-(IC4A-QH*)") (class "Default")
      (node (ref "IC4") (pin "9") (pinfunction "QH*_9") (pintype "tri_state"))
      (node (ref "IC5") (pin "14") (pinfunction "SER_14") (pintype "input"))
    )
    (net (code "51") (name "Net-(IC5A-QA)") (class "Default")
      (node (ref "IC5") (pin "15") (pinfunction "QA_15") (pintype "tri_state"))
      (node (ref "IC7") (pin "1") (pinfunction "I1_1") (pintype "input"))
    )
    (net (code "52") (name "Net-(IC5A-QB)") (class "Default")
      (node (ref "IC5") (pin "1") (pinfunction "QB_1") (pintype "tri_state"))
      (node (ref "IC7") (pin "2") (pinfunction "I2_2") (pintype "input"))
    )
    (net (code "53") (name "Net-(IC5A-QC)") (class "Default")
      (node (ref "IC5") (pin "2") (pinfunction "QC_2") (pintype "tri_state"))
      (node (ref "IC7") (pin "3") (pinfunction "I3_3") (pintype "input"))
    )
    (net (code "54") (name "Net-(IC5A-QD)") (class "Default")
      (node (ref "IC5") (pin "3") (pinfunction "QD_3") (pintype "tri_state"))
      (node (ref "IC7") (pin "4") (pinfunction "I4_4") (pintype "input"))
    )
    (net (code "55") (name "Net-(IC5A-QE)") (class "Default")
      (node (ref "IC5") (pin "4") (pinfunction "QE_4") (pintype "tri_state"))
      (node (ref "IC7") (pin "5") (pinfunction "I5_5") (pintype "input"))
    )
    (net (code "56") (name "Net-(IC5A-QF)") (class "Default")
      (node (ref "IC5") (pin "5") (pinfunction "QF_5") (pintype "tri_state"))
      (node (ref "IC7") (pin "6") (pinfunction "I6_6") (pintype "input"))
    )
    (net (code "57") (name "Net-(IC5A-QG)") (class "Default")
      (node (ref "IC5") (pin "6") (pinfunction "QG_6") (pintype "tri_state"))
      (node (ref "IC7") (pin "7") (pinfunction "I7_7") (pintype "input"))
    )
    (net (code "58") (name "Net-(IC5A-QH)") (class "Default")
      (node (ref "IC5") (pin "7") (pinfunction "QH_7") (pintype "tri_state"))
      (node (ref "IC7") (pin "8") (pinfunction "I8_8") (pintype "input"))
    )
    (net (code "59") (name "Net-(IC10A-QA)") (class "Default")
      (node (ref "IC10") (pin "15") (pinfunction "QA_15") (pintype "tri_state"))
      (node (ref "IC3") (pin "1") (pinfunction "I1_1") (pintype "input"))
    )
    (net (code "60") (name "Net-(IC10A-QB)") (class "Default")
      (node (ref "IC10") (pin "1") (pinfunction "QB_1") (pintype "tri_state"))
      (node (ref "IC3") (pin "2") (pinfunction "I2_2") (pintype "input"))
    )
    (net (code "61") (name "Net-(IC10A-QC)") (class "Default")
      (node (ref "IC10") (pin "2") (pinfunction "QC_2") (pintype "tri_state"))
      (node (ref "IC3") (pin "3") (pinfunction "I3_3") (pintype "input"))
    )
    (net (code "62") (name "Net-(IC10A-QD)") (class "Default")
      (node (ref "IC10") (pin "3") (pinfunction "QD_3") (pintype "tri_state"))
      (node (ref "IC3") (pin "4") (pinfunction "I4_4") (pintype "input"))
    )
    (net (code "63") (name "Net-(IC10A-QE)") (class "Default")
      (node (ref "IC10") (pin "4") (pinfunction "QE_4") (pintype "tri_state"))
      (node (ref "IC3") (pin "5") (pinfunction "I5_5") (pintype "input"))
    )
    (net (code "64") (name "Net-(IC10A-QF)") (class "Default")
      (node (ref "IC10") (pin "5") (pinfunction "QF_5") (pintype "tri_state"))
      (node (ref "IC3") (pin "6") (pinfunction "I6_6") (pintype "input"))
    )
    (net (code "65") (name "Net-(IC10A-QG)") (class "Default")
      (node (ref "IC10") (pin "6") (pinfunction "QG_6") (pintype "tri_state"))
      (node (ref "IC3") (pin "7") (pinfunction "I7_7") (pintype "input"))
    )
    (net (code "66") (name "Net-(IC10A-QH)") (class "Default")
      (node (ref "IC10") (pin "7") (pinfunction "QH_7") (pintype "tri_state"))
      (node (ref "IC3") (pin "8") (pinfunction "I8_8") (pintype "input"))
    )
    (net (code "67") (name "Net-(IC10A-QH*)") (class "Default")
      (node (ref "IC10") (pin "9") (pinfunction "QH*_9") (pintype "tri_state"))
      (node (ref "IC11") (pin "14") (pinfunction "SER_14") (pintype "input"))
    )
    (net (code "68") (name "Net-(IC11A-QA)") (class "Default")
      (node (ref "IC11") (pin "15") (pinfunction "QA_15") (pintype "tri_state"))
      (node (ref "IC8") (pin "1") (pinfunction "I1_1") (pintype "input"))
    )
    (net (code "69") (name "Net-(IC11A-QB)") (class "Default")
      (node (ref "IC11") (pin "1") (pinfunction "QB_1") (pintype "tri_state"))
      (node (ref "IC8") (pin "2") (pinfunction "I2_2") (pintype "input"))
    )
    (net (code "70") (name "Net-(IC11A-QC)") (class "Default")
      (node (ref "IC11") (pin "2") (pinfunction "QC_2") (pintype "tri_state"))
      (node (ref "IC8") (pin "3") (pinfunction "I3_3") (pintype "input"))
    )
    (net (code "71") (name "Net-(IC11A-QD)") (class "Default")
      (node (ref "IC11") (pin "3") (pinfunction "QD_3") (pintype "tri_state"))
      (node (ref "IC8") (pin "4") (pinfunction "I4_4") (pintype "input"))
    )
    (net (code "72") (name "Net-(IC11A-QE)") (class "Default")
      (node (ref "IC11") (pin "4") (pinfunction "QE_4") (pintype "tri_state"))
      (node (ref "IC8") (pin "5") (pinfunction "I5_5") (pintype "input"))
    )
    (net (code "73") (name "Net-(IC11A-QF)") (class "Default")
      (node (ref "IC11") (pin "5") (pinfunction "QF_5") (pintype "tri_state"))
      (node (ref "IC8") (pin "6") (pinfunction "I6_6") (pintype "input"))
    )
    (net (code "74") (name "Net-(IC11A-QG)") (class "Default")
      (node (ref "IC11") (pin "6") (pinfunction "QG_6") (pintype "tri_state"))
      (node (ref "IC8") (pin "7") (pinfunction "I7_7") (pintype "input"))
    )
    (net (code "75") (name "Net-(IC11A-QH)") (class "Default")
      (node (ref "IC11") (pin "7") (pinfunction "QH_7") (pintype "tri_state"))
      (node (ref "IC8") (pin "8") (pinfunction "I8_8") (pintype "input"))
    )
    (net (code "76") (name "Net-(IC11A-QH*)") (class "Default")
      (node (ref "IC11") (pin "9") (pinfunction "QH*_9") (pintype "tri_state"))
      (node (ref "IC12") (pin "14") (pinfunction "SER_14") (pintype "input"))
    )
    (net (code "77") (name "Net-(IC12A-QA)") (class "Default")
      (node (ref "IC12") (pin "15") (pinfunction "QA_15") (pintype "tri_state"))
      (node (ref "IC9") (pin "1") (pinfunction "I1_1") (pintype "input"))
    )
    (net (code "78") (name "Net-(IC12A-QB)") (class "Default")
      (node (ref "IC12") (pin "1") (pinfunction "QB_1") (pintype "tri_state"))
      (node (ref "IC9") (pin "2") (pinfunction "I2_2") (pintype "input"))
    )
    (net (code "79") (name "Net-(IC12A-QC)") (class "Default")
      (node (ref "IC12") (pin "2") (pinfunction "QC_2") (pintype "tri_state"))
      (node (ref "IC9") (pin "3") (pinfunction "I3_3") (pintype "input"))
    )
    (net (code "80") (name "Net-(IC12A-QD)") (class "Default")
      (node (ref "IC12") (pin "3") (pinfunction "QD_3") (pintype "tri_state"))
      (node (ref "IC9") (pin "4") (pinfunction "I4_4") (pintype "input"))
    )
    (net (code "81") (name "Net-(IC12A-QE)") (class "Default")
      (node (ref "IC12") (pin "4") (pinfunction "QE_4") (pintype "tri_state"))
      (node (ref "IC9") (pin "5") (pinfunction "I5_5") (pintype "input"))
    )
    (net (code "82") (name "Net-(IC12A-QF)") (class "Default")
      (node (ref "IC12") (pin "5") (pinfunction "QF_5") (pintype "tri_state"))
      (node (ref "IC9") (pin "6") (pinfunction "I6_6") (pintype "input"))
    )
    (net (code "83") (name "Net-(IC12A-QG)") (class "Default")
      (node (ref "IC12") (pin "6") (pinfunction "QG_6") (pintype "tri_state"))
      (node (ref "IC9") (pin "7") (pinfunction "I7_7") (pintype "input"))
    )
    (net (code "84") (name "Net-(IC12A-QH)") (class "Default")
      (node (ref "IC12") (pin "7") (pinfunction "QH_7") (pintype "tri_state"))
      (node (ref "IC9") (pin "8") (pinfunction "I8_8") (pintype "input"))
    )
    (net (code "85") (name "Net-(IC13A-O)") (class "Default")
      (node (ref "IC13") (pin "3") (pinfunction "O_3") (pintype "output"))
      (node (ref "IC13") (pin "9") (pinfunction "I0_9") (pintype "input"))
    )
    (net (code "86") (name "Net-(IC16A-QH*)") (class "Default")
      (node (ref "IC16") (pin "9") (pinfunction "QH*_9") (pintype "tri_state"))
      (node (ref "IC17") (pin "14") (pinfunction "SER_14") (pintype "input"))
    )
    (net (code "87") (name "Net-(IC19-FB)") (class "Default")
      (node (ref "IC19") (pin "4") (pinfunction "FB_4") (pintype "input"))
      (node (ref "R1") (pin "1") (pinfunction "1_1") (pintype "passive"))
      (node (ref "R2") (pin "2") (pinfunction "2_2") (pintype "passive"))
    )
    (net (code "88") (name "Net-(IC19-OUT)") (class "Default")
      (node (ref "D2") (pin "C") (pinfunction "C_C") (pintype "passive"))
      (node (ref "IC19") (pin "2") (pinfunction "OUT_2") (pintype "output"))
      (node (ref "L2") (pin "1") (pinfunction "1_1") (pintype "bidirectional"))
    )
    (net (code "89") (name "Net-(IC20-VI)") (class "Default")
      (node (ref "C11") (pin "1") (pinfunction "1_1") (pintype "passive"))
      (node (ref "C14") (pin "+") (pinfunction "+_+") (pintype "passive"))
      (node (ref "IC20") (pin "1") (pinfunction "VI_1") (pintype "input"))
      (node (ref "L2") (pin "2") (pinfunction "2_2") (pintype "bidirectional"))
      (node (ref "R2") (pin "1") (pinfunction "1_1") (pintype "passive"))
    )
    (net (code "90") (name "Net-(IC21A-C1+)") (class "Default")
      (node (ref "C15") (pin "1") (pinfunction "1_1") (pintype "passive"))
      (node (ref "IC21") (pin "1") (pinfunction "C1+_1") (pintype "bidirectional"))
    )
    (net (code "91") (name "Net-(IC21A-C1-)") (class "Default")
      (node (ref "C15") (pin "2") (pinfunction "2_2") (pintype "passive"))
      (node (ref "IC21") (pin "3") (pinfunction "C1-_3") (pintype "bidirectional"))
    )
    (net (code "92") (name "Net-(IC21A-C2+)") (class "Default")
      (node (ref "C10") (pin "1") (pinfunction "1_1") (pintype "passive"))
      (node (ref "IC21") (pin "4") (pinfunction "C2+_4") (pintype "bidirectional"))
    )
    (net (code "93") (name "Net-(IC21A-C2-)") (class "Default")
      (node (ref "C10") (pin "2") (pinfunction "2_2") (pintype "passive"))
      (node (ref "IC21") (pin "5") (pinfunction "C2-_5") (pintype "bidirectional"))
    )
    (net (code "94") (name "Net-(IC21A-R1IN)") (class "Default")
      (node (ref "IC21") (pin "13") (pinfunction "R1IN_13") (pintype "input"))
      (node (ref "X4") (pin "2") (pinfunction "S_2") (pintype "passive"))
    )
    (net (code "95") (name "Net-(IC21A-T1OUT)") (class "Default")
      (node (ref "IC21") (pin "14") (pinfunction "T1OUT_14") (pintype "output"))
      (node (ref "X4") (pin "1") (pinfunction "S_1") (pintype "passive"))
    )
    (net (code "96") (name "Net-(IC21A-V+)") (class "Default")
      (node (ref "C17") (pin "1") (pinfunction "1_1") (pintype "passive"))
      (node (ref "IC21") (pin "2") (pinfunction "V+_2") (pintype "bidirectional"))
    )
    (net (code "97") (name "Net-(IC21A-V-)") (class "Default")
      (node (ref "C18") (pin "1") (pinfunction "1_1") (pintype "passive"))
      (node (ref "IC21") (pin "6") (pinfunction "V-_6") (pintype "bidirectional"))
    )
    (net (code "98") (name "Net-(IC22A-A)") (class "Default")
      (node (ref "IC22") (pin "6") (pinfunction "A_6") (pintype "passive"))
      (node (ref "R10") (pin "1") (pinfunction "1_1") (pintype "passive"))
      (node (ref "X3") (pin "2") (pinfunction "S_2") (pintype "passive"))
    )
    (net (code "99") (name "Net-(IC22A-B)") (class "Default")
      (node (ref "IC22") (pin "7") (pinfunction "B_7") (pintype "passive"))
      (node (ref "R10") (pin "2") (pinfunction "2_2") (pintype "passive"))
      (node (ref "X3") (pin "1") (pinfunction "S_1") (pintype "passive"))
    )
    (net (code "100") (name "Net-(LED1-K)") (class "Default")
      (node (ref "LED1") (pin "1") (pinfunction "K_1") (pintype "bidirectional"))
      (node (ref "R9") (pin "1") (pinfunction "1_1") (pintype "passive"))
    )
    (net (code "101") (name "Net-(R5-Pad1)") (class "Default")
      (node (ref "R5") (pin "1") (pinfunction "1_1") (pintype "passive"))
      (node (ref "R6") (pin "2") (pinfunction "2_2") (pintype "passive"))
    )
    (net (code "102") (name "Net-(S1-P)") (class "Default")
      (node (ref "S1") (pin "3") (pinfunction "P_3") (pintype "passive"))
      (node (ref "S1") (pin "4") (pinfunction "P1_4") (pintype "passive"))
      (node (ref "U$1") (pin "P$26") (pinfunction "PB10_P$26") (pintype "bidirectional"))
    )
    (net (code "103") (name "Net-(S2-P)") (class "Default")
      (node (ref "S2") (pin "3") (pinfunction "P_3") (pintype "passive"))
      (node (ref "S2") (pin "4") (pinfunction "P1_4") (pintype "passive"))
      (node (ref "U$1") (pin "P$27") (pinfunction "PB1_P$27") (pintype "bidirectional"))
    )
    (net (code "104") (name "Net-(S3-P)") (class "Default")
      (node (ref "S3") (pin "3") (pinfunction "P_3") (pintype "passive"))
      (node (ref "S3") (pin "4") (pinfunction "P1_4") (pintype "passive"))
      (node (ref "U$1") (pin "P$28") (pinfunction "PB0_P$28") (pintype "bidirectional"))
    )
    (net (code "105") (name "Net-(STATUS-A)") (class "Default")
      (node (ref "R12") (pin "2") (pinfunction "2_2") (pintype "passive"))
      (node (ref "STATUS") (pin "2") (pinfunction "A_2") (pintype "bidirectional"))
    )
    (net (code "106") (name "Net-(T1-B)") (class "Default")
      (node (ref "R3") (pin "1") (pinfunction "1_1") (pintype "passive"))
      (node (ref "T1") (pin "1") (pinfunction "B_1") (pintype "passive"))
    )
    (net (code "107") (name "Net-(T1-C)") (class "Default")
      (node (ref "T1") (pin "3") (pinfunction "C_3") (pintype "passive"))
      (node (ref "U$1") (pin "P$24") (pinfunction "RESET_P$24") (pintype "bidirectional"))
    )
    (net (code "108") (name "Net-(T2-B)") (class "Default")
      (node (ref "Q1") (pin "E") (pinfunction "E_E") (pintype "passive"))
      (node (ref "R5") (pin "2") (pinfunction "2_2") (pintype "passive"))
      (node (ref "T2") (pin "1") (pinfunction "B_1") (pintype "passive"))
    )
    (net (code "109") (name "Net-(T2-C)") (class "Default")
      (node (ref "Q1") (pin "B") (pinfunction "B_B") (pintype "passive"))
      (node (ref "R4") (pin "1") (pinfunction "1_1") (pintype "passive"))
      (node (ref "T2") (pin "3") (pinfunction "C_3") (pintype "passive"))
    )
    (net (code "110") (name "Net-(T3-B)") (class "Default")
      (node (ref "R8") (pin "1") (pinfunction "1_1") (pintype "passive"))
      (node (ref "T3") (pin "1") (pinfunction "B_1") (pintype "passive"))
    )
    (net (code "111") (name "Net-(T3-C)") (class "Default")
      (node (ref "D5") (pin "A") (pinfunction "A_A") (pintype "passive"))
      (node (ref "T3") (pin "3") (pinfunction "C_3") (pintype "passive"))
    )
    (net (code "112") (name "Net-(TX-A)") (class "Default")
      (node (ref "R11") (pin "2") (pinfunction "2_2") (pintype "passive"))
      (node (ref "TX") (pin "2") (pinfunction "A_2") (pintype "bidirectional"))
    )
    (net (code "113") (name "Net-(U$1-3.3V)") (class "Default")
      (node (ref "C13") (pin "2") (pinfunction "2_2") (pintype "passive"))
      (node (ref "U$1") (pin "P$23") (pinfunction "3.3V_P$23") (pintype "bidirectional"))
    )
    (net (code "114") (name "Net-(U$1-PB3)") (class "Default")
      (node (ref "SW") (pin "4") (pinfunction "4_4") (pintype "passive"))
      (node (ref "U$1") (pin "P$11") (pinfunction "PB3_P$11") (pintype "bidirectional"))
    )
    (net (code "115") (name "Net-(U$1-PB4)") (class "Default")
      (node (ref "SW") (pin "3") (pinfunction "3_3") (pintype "passive"))
      (node (ref "U$1") (pin "P$12") (pinfunction "PB4_P$12") (pintype "bidirectional"))
    )
    (net (code "116") (name "Net-(U$1-PB5)") (class "Default")
      (node (ref "SW") (pin "2") (pinfunction "2_2") (pintype "passive"))
      (node (ref "U$1") (pin "P$13") (pinfunction "PB5_P$13") (pintype "bidirectional"))
    )
    (net (code "117") (name "Net-(U$1-PB6)") (class "Default")
      (node (ref "SW") (pin "1") (pinfunction "1_1") (pintype "passive"))
      (node (ref "U$1") (pin "P$14") (pinfunction "PB6_P$14") (pintype "bidirectional"))
    )
    (net (code "118") (name "Net-(U$1-PB7)") (class "Default")
      (node (ref "R11") (pin "1") (pinfunction "1_1") (pintype "passive"))
      (node (ref "U$1") (pin "P$15") (pinfunction "PB7_P$15") (pintype "bidirectional"))
    )
    (net (code "119") (name "Net-(U$1-PB8)") (class "Default")
      (node (ref "R12") (pin "1") (pinfunction "1_1") (pintype "passive"))
      (node (ref "U$1") (pin "P$16") (pinfunction "PB8_P$16") (pintype "bidirectional"))
    )
    (net (code "120") (name "Net-(U$1-PB11)") (class "Default")
      (node (ref "R3") (pin "2") (pinfunction "2_2") (pintype "passive"))
      (node (ref "U$1") (pin "P$25") (pinfunction "PB11_P$25") (pintype "bidirectional"))
    )
    (net (code "121") (name "Net-(X1B-KL)") (class "Default")
      (node (ref "Q2") (pin "D") (pinfunction "D_D") (pintype "passive"))
      (node (ref "X1") (pin "2") (pinfunction "KL_2") (pintype "passive"))
    )
    (net (code "122") (name "Net-(X1C-KL)") (class "Default")
      (node (ref "F1") (pin "1") (pinfunction "1_1") (pintype "passive"))
      (node (ref "X1") (pin "3") (pinfunction "KL_3") (pintype "passive"))
    )
    (net (code "123") (name "OE_RESET") (class "Default")
      (node (ref "IC1") (pin "13") (pinfunction "G_13") (pintype "input"))
      (node (ref "IC13") (pin "8") (pinfunction "O_8") (pintype "output"))
      (node (ref "IC4") (pin "13") (pinfunction "G_13") (pintype "input"))
      (node (ref "IC5") (pin "13") (pinfunction "G_13") (pintype "input"))
    )
    (net (code "124") (name "OE_SET") (class "Default")
      (node (ref "IC10") (pin "13") (pinfunction "G_13") (pintype "input"))
      (node (ref "IC11") (pin "13") (pinfunction "G_13") (pintype "input"))
      (node (ref "IC12") (pin "13") (pinfunction "G_13") (pintype "input"))
      (node (ref "IC13") (pin "6") (pinfunction "O_6") (pintype "output"))
    )
    (net (code "125") (name "RESET_01") (class "Default")
      (node (ref "CON3") (pin "19") (pinfunction "19_19") (pintype "passive"))
      (node (ref "CON4") (pin "21") (pinfunction "21_21") (pintype "passive"))
      (node (ref "IC2") (pin "18") (pinfunction "O1_18") (pintype "open_collector"))
    )
    (net (code "126") (name "RESET_02") (class "Default")
      (node (ref "CON3") (pin "21") (pinfunction "21_21") (pintype "passive"))
      (node (ref "CON4") (pin "22") (pinfunction "22_22") (pintype "passive"))
      (node (ref "IC2") (pin "17") (pinfunction "O2_17") (pintype "open_collector"))
    )
    (net (code "127") (name "RESET_03") (class "Default")
      (node (ref "CON3") (pin "23") (pinfunction "23_23") (pintype "passive"))
      (node (ref "CON4") (pin "23") (pinfunction "23_23") (pintype "passive"))
      (node (ref "IC2") (pin "16") (pinfunction "O3_16") (pintype "open_collector"))
    )
    (net (code "128") (name "RESET_04") (class "Default")
      (node (ref "CON3") (pin "25") (pinfunction "25_25") (pintype "passive"))
      (node (ref "CON4") (pin "24") (pinfunction "24_24") (pintype "passive"))
      (node (ref "IC2") (pin "15") (pinfunction "O4_15") (pintype "open_collector"))
    )
    (net (code "129") (name "RESET_05") (class "Default")
      (node (ref "CON3") (pin "27") (pinfunction "27_27") (pintype "passive"))
      (node (ref "CON4") (pin "25") (pinfunction "25_25") (pintype "passive"))
      (node (ref "IC2") (pin "14") (pinfunction "O5_14") (pintype "open_collector"))
    )
    (net (code "130") (name "RESET_06") (class "Default")
      (node (ref "CON3") (pin "29") (pinfunction "29_29") (pintype "passive"))
      (node (ref "CON4") (pin "26") (pinfunction "26_26") (pintype "passive"))
      (node (ref "IC2") (pin "13") (pinfunction "O6_13") (pintype "open_collector"))
    )
    (net (code "131") (name "RESET_07") (class "Default")
      (node (ref "CON3") (pin "31") (pinfunction "31_31") (pintype "passive"))
      (node (ref "CON4") (pin "27") (pinfunction "27_27") (pintype "passive"))
      (node (ref "IC2") (pin "12") (pinfunction "O7_12") (pintype "open_collector"))
    )
    (net (code "132") (name "RESET_08") (class "Default")
      (node (ref "CON3") (pin "33") (pinfunction "33_33") (pintype "passive"))
      (node (ref "CON4") (pin "28") (pinfunction "28_28") (pintype "passive"))
      (node (ref "IC2") (pin "11") (pinfunction "O8_11") (pintype "open_collector"))
    )
    (net (code "133") (name "RESET_09") (class "Default")
      (node (ref "CON3") (pin "35") (pinfunction "35_35") (pintype "passive"))
      (node (ref "CON4") (pin "29") (pinfunction "29_29") (pintype "passive"))
      (node (ref "IC6") (pin "18") (pinfunction "O1_18") (pintype "open_collector"))
    )
    (net (code "134") (name "RESET_10") (class "Default")
      (node (ref "CON3") (pin "37") (pinfunction "37_37") (pintype "passive"))
      (node (ref "CON4") (pin "30") (pinfunction "30_30") (pintype "passive"))
      (node (ref "IC6") (pin "17") (pinfunction "O2_17") (pintype "open_collector"))
    )
    (net (code "135") (name "RESET_11") (class "Default")
      (node (ref "CON3") (pin "39") (pinfunction "39_39") (pintype "passive"))
      (node (ref "CON4") (pin "31") (pinfunction "31_31") (pintype "passive"))
      (node (ref "IC6") (pin "16") (pinfunction "O3_16") (pintype "open_collector"))
    )
    (net (code "136") (name "RESET_12") (class "Default")
      (node (ref "CON3") (pin "41") (pinfunction "41_41") (pintype "passive"))
      (node (ref "CON4") (pin "32") (pinfunction "32_32") (pintype "passive"))
      (node (ref "IC6") (pin "15") (pinfunction "O4_15") (pintype "open_collector"))
    )
    (net (code "137") (name "RESET_13") (class "Default")
      (node (ref "CON3") (pin "43") (pinfunction "43_43") (pintype "passive"))
      (node (ref "CON4") (pin "33") (pinfunction "33_33") (pintype "passive"))
      (node (ref "IC6") (pin "14") (pinfunction "O5_14") (pintype "open_collector"))
    )
    (net (code "138") (name "RESET_14") (class "Default")
      (node (ref "CON3") (pin "45") (pinfunction "45_45") (pintype "passive"))
      (node (ref "CON4") (pin "34") (pinfunction "34_34") (pintype "passive"))
      (node (ref "IC6") (pin "13") (pinfunction "O6_13") (pintype "open_collector"))
    )
    (net (code "139") (name "RESET_15") (class "Default")
      (node (ref "CON3") (pin "47") (pinfunction "47_47") (pintype "passive"))
      (node (ref "CON4") (pin "35") (pinfunction "35_35") (pintype "passive"))
      (node (ref "IC6") (pin "12") (pinfunction "O7_12") (pintype "open_collector"))
    )
    (net (code "140") (name "RESET_16") (class "Default")
      (node (ref "CON3") (pin "49") (pinfunction "49_49") (pintype "passive"))
      (node (ref "CON4") (pin "36") (pinfunction "36_36") (pintype "passive"))
      (node (ref "IC6") (pin "11") (pinfunction "O8_11") (pintype "open_collector"))
    )
    (net (code "141") (name "RESET_17") (class "Default")
      (node (ref "CON4") (pin "37") (pinfunction "37_37") (pintype "passive"))
      (node (ref "IC7") (pin "18") (pinfunction "O1_18") (pintype "open_collector"))
    )
    (net (code "142") (name "RESET_18") (class "Default")
      (node (ref "CON4") (pin "38") (pinfunction "38_38") (pintype "passive"))
      (node (ref "IC7") (pin "17") (pinfunction "O2_17") (pintype "open_collector"))
    )
    (net (code "143") (name "RESET_19") (class "Default")
      (node (ref "CON4") (pin "39") (pinfunction "39_39") (pintype "passive"))
      (node (ref "IC7") (pin "16") (pinfunction "O3_16") (pintype "open_collector"))
    )
    (net (code "144") (name "RESET_20") (class "Default")
      (node (ref "CON4") (pin "40") (pinfunction "40_40") (pintype "passive"))
      (node (ref "IC7") (pin "15") (pinfunction "O4_15") (pintype "open_collector"))
    )
    (net (code "145") (name "RS485_EN") (class "Default")
      (node (ref "IC22") (pin "2") (pinfunction "RE/_2") (pintype "input"))
      (node (ref "IC22") (pin "3") (pinfunction "DE_3") (pintype "input"))
      (node (ref "U$1") (pin "P$35") (pinfunction "PA1_P$35") (pintype "bidirectional"))
    )
    (net (code "146") (name "RX") (class "Default")
      (node (ref "IC21") (pin "12") (pinfunction "R1OUT_12") (pintype "output"))
      (node (ref "IC22") (pin "1") (pinfunction "RO_1") (pintype "output"))
      (node (ref "U$1") (pin "P$7") (pinfunction "PA10_P$7") (pintype "bidirectional"))
      (node (ref "X2") (pin "2") (pinfunction "S_2") (pintype "passive"))
    )
    (net (code "147") (name "SET_01") (class "Default")
      (node (ref "CON3") (pin "20") (pinfunction "20_20") (pintype "passive"))
      (node (ref "CON4") (pin "1") (pinfunction "1_1") (pintype "passive"))
      (node (ref "IC3") (pin "18") (pinfunction "O1_18") (pintype "open_collector"))
    )
    (net (code "148") (name "SET_02") (class "Default")
      (node (ref "CON3") (pin "22") (pinfunction "22_22") (pintype "passive"))
      (node (ref "CON4") (pin "2") (pinfunction "2_2") (pintype "passive"))
      (node (ref "IC3") (pin "17") (pinfunction "O2_17") (pintype "open_collector"))
    )
    (net (code "149") (name "SET_03") (class "Default")
      (node (ref "CON3") (pin "24") (pinfunction "24_24") (pintype "passive"))
      (node (ref "CON4") (pin "3") (pinfunction "3_3") (pintype "passive"))
      (node (ref "IC3") (pin "16") (pinfunction "O3_16") (pintype "open_collector"))
    )
    (net (code "150") (name "SET_04") (class "Default")
      (node (ref "CON3") (pin "26") (pinfunction "26_26") (pintype "passive"))
      (node (ref "CON4") (pin "4") (pinfunction "4_4") (pintype "passive"))
      (node (ref "IC3") (pin "15") (pinfunction "O4_15") (pintype "open_collector"))
    )
    (net (code "151") (name "SET_05") (class "Default")
      (node (ref "CON3") (pin "28") (pinfunction "28_28") (pintype "passive"))
      (node (ref "CON4") (pin "5") (pinfunction "5_5") (pintype "passive"))
      (node (ref "IC3") (pin "14") (pinfunction "O5_14") (pintype "open_collector"))
    )
    (net (code "152") (name "SET_06") (class "Default")
      (node (ref "CON3") (pin "30") (pinfunction "30_30") (pintype "passive"))
      (node (ref "CON4") (pin "6") (pinfunction "6_6") (pintype "passive"))
      (node (ref "IC3") (pin "13") (pinfunction "O6_13") (pintype "open_collector"))
    )
    (net (code "153") (name "SET_07") (class "Default")
      (node (ref "CON3") (pin "32") (pinfunction "32_32") (pintype "passive"))
      (node (ref "CON4") (pin "7") (pinfunction "7_7") (pintype "passive"))
      (node (ref "IC3") (pin "12") (pinfunction "O7_12") (pintype "open_collector"))
    )
    (net (code "154") (name "SET_08") (class "Default")
      (node (ref "CON3") (pin "34") (pinfunction "34_34") (pintype "passive"))
      (node (ref "CON4") (pin "8") (pinfunction "8_8") (pintype "passive"))
      (node (ref "IC3") (pin "11") (pinfunction "O8_11") (pintype "open_collector"))
    )
    (net (code "155") (name "SET_09") (class "Default")
      (node (ref "CON3") (pin "36") (pinfunction "36_36") (pintype "passive"))
      (node (ref "CON4") (pin "9") (pinfunction "9_9") (pintype "passive"))
      (node (ref "IC8") (pin "18") (pinfunction "O1_18") (pintype "open_collector"))
    )
    (net (code "156") (name "SET_10") (class "Default")
      (node (ref "CON3") (pin "38") (pinfunction "38_38") (pintype "passive"))
      (node (ref "CON4") (pin "10") (pinfunction "10_10") (pintype "passive"))
      (node (ref "IC8") (pin "17") (pinfunction "O2_17") (pintype "open_collector"))
    )
    (net (code "157") (name "SET_11") (class "Default")
      (node (ref "CON3") (pin "40") (pinfunction "40_40") (pintype "passive"))
      (node (ref "CON4") (pin "11") (pinfunction "11_11") (pintype "passive"))
      (node (ref "IC8") (pin "16") (pinfunction "O3_16") (pintype "open_collector"))
    )
    (net (code "158") (name "SET_12") (class "Default")
      (node (ref "CON3") (pin "42") (pinfunction "42_42") (pintype "passive"))
      (node (ref "CON4") (pin "12") (pinfunction "12_12") (pintype "passive"))
      (node (ref "IC8") (pin "15") (pinfunction "O4_15") (pintype "open_collector"))
    )
    (net (code "159") (name "SET_13") (class "Default")
      (node (ref "CON3") (pin "44") (pinfunction "44_44") (pintype "passive"))
      (node (ref "CON4") (pin "13") (pinfunction "13_13") (pintype "passive"))
      (node (ref "IC8") (pin "14") (pinfunction "O5_14") (pintype "open_collector"))
    )
    (net (code "160") (name "SET_14") (class "Default")
      (node (ref "CON3") (pin "46") (pinfunction "46_46") (pintype "passive"))
      (node (ref "CON4") (pin "14") (pinfunction "14_14") (pintype "passive"))
      (node (ref "IC8") (pin "13") (pinfunction "O6_13") (pintype "open_collector"))
    )
    (net (code "161") (name "SET_15") (class "Default")
      (node (ref "CON3") (pin "48") (pinfunction "48_48") (pintype "passive"))
      (node (ref "CON4") (pin "15") (pinfunction "15_15") (pintype "passive"))
      (node (ref "IC8") (pin "12") (pinfunction "O7_12") (pintype "open_collector"))
    )
    (net (code "162") (name "SET_16") (class "Default")
      (node (ref "CON3") (pin "50") (pinfunction "50_50") (pintype "passive"))
      (node (ref "CON4") (pin "16") (pinfunction "16_16") (pintype "passive"))
      (node (ref "IC8") (pin "11") (pinfunction "O8_11") (pintype "open_collector"))
    )
    (net (code "163") (name "SET_17") (class "Default")
      (node (ref "CON4") (pin "17") (pinfunction "17_17") (pintype "passive"))
      (node (ref "IC9") (pin "18") (pinfunction "O1_18") (pintype "open_collector"))
    )
    (net (code "164") (name "SET_18") (class "Default")
      (node (ref "CON4") (pin "18") (pinfunction "18_18") (pintype "passive"))
      (node (ref "IC9") (pin "17") (pinfunction "O2_17") (pintype "open_collector"))
    )
    (net (code "165") (name "SET_19") (class "Default")
      (node (ref "CON4") (pin "19") (pinfunction "19_19") (pintype "passive"))
      (node (ref "IC9") (pin "16") (pinfunction "O3_16") (pintype "open_collector"))
    )
    (net (code "166") (name "SET_20") (class "Default")
      (node (ref "CON4") (pin "20") (pinfunction "20_20") (pintype "passive"))
      (node (ref "IC9") (pin "15") (pinfunction "O4_15") (pintype "open_collector"))
    )
    (net (code "167") (name "SET{slash}RESET") (class "Default")
      (node (ref "IC13") (pin "1") (pinfunction "I0_1") (pintype "input"))
      (node (ref "IC13") (pin "2") (pinfunction "I1_2") (pintype "input"))
      (node (ref "IC13") (pin "4") (pinfunction "I0_4") (pintype "input"))
      (node (ref "U$1") (pin "P$33") (pinfunction "PA3_P$33") (pintype "bidirectional"))
    )
    (net (code "168") (name "SPALTEN_CLK") (class "Default")
      (node (ref "IC16") (pin "11") (pinfunction "SCK_11") (pintype "input"))
      (node (ref "IC17") (pin "11") (pinfunction "SCK_11") (pintype "input"))
      (node (ref "U$1") (pin "P$2") (pinfunction "PB13_P$2") (pintype "bidirectional"))
    )
    (net (code "169") (name "SPALTEN_D") (class "Default")
      (node (ref "IC16") (pin "14") (pinfunction "SER_14") (pintype "input"))
      (node (ref "U$1") (pin "P$4") (pinfunction "PB15_P$4") (pintype "bidirectional"))
    )
    (net (code "170") (name "SPALTEN_LATCH") (class "Default")
      (node (ref "IC16") (pin "12") (pinfunction "RCK_12") (pintype "input"))
      (node (ref "IC17") (pin "12") (pinfunction "RCK_12") (pintype "input"))
      (node (ref "U$1") (pin "P$3") (pinfunction "PB14_P$3") (pintype "bidirectional"))
    )
    (net (code "171") (name "SPALTEN_OE") (class "Default")
      (node (ref "IC16") (pin "13") (pinfunction "G_13") (pintype "input"))
      (node (ref "IC17") (pin "13") (pinfunction "G_13") (pintype "input"))
      (node (ref "U$1") (pin "P$1") (pinfunction "PB12_P$1") (pintype "bidirectional"))
    )
    (net (code "172") (name "SPALTEN_RESET") (class "Default")
      (node (ref "IC16") (pin "10") (pinfunction "SCL_10") (pintype "input"))
      (node (ref "IC17") (pin "10") (pinfunction "SCL_10") (pintype "input"))
      (node (ref "U$1") (pin "P$5") (pinfunction "PA8_P$5") (pintype "bidirectional"))
    )
    (net (code "173") (name "TX") (class "Default")
      (node (ref "IC21") (pin "11") (pinfunction "T1IN_11") (pintype "input"))
      (node (ref "IC22") (pin "4") (pinfunction "DI_4") (pintype "input"))
      (node (ref "U$1") (pin "P$6") (pinfunction "PA9_P$6") (pintype "bidirectional"))
      (node (ref "X2") (pin "3") (pinfunction "S_3") (pintype "passive"))
    )
    (net (code "174") (name "VCC") (class "Default")
      (node (ref "C1") (pin "1") (pinfunction "1_1") (pintype "passive"))
      (node (ref "C12") (pin "1") (pinfunction "1_1") (pintype "passive"))
      (node (ref "C16") (pin "2") (pinfunction "2_2") (pintype "passive"))
      (node (ref "C19") (pin "1") (pinfunction "1_1") (pintype "passive"))
      (node (ref "C2") (pin "1") (pinfunction "1_1") (pintype "passive"))
      (node (ref "C3") (pin "1") (pinfunction "1_1") (pintype "passive"))
      (node (ref "C4") (pin "1") (pinfunction "1_1") (pintype "passive"))
      (node (ref "C5") (pin "1") (pinfunction "1_1") (pintype "passive"))
      (node (ref "C6") (pin "1") (pinfunction "1_1") (pintype "passive"))
      (node (ref "C7") (pin "1") (pinfunction "1_1") (pintype "passive"))
      (node (ref "C8") (pin "1") (pinfunction "1_1") (pintype "passive"))
      (node (ref "CON3") (pin "5") (pinfunction "5_5") (pintype "passive"))
      (node (ref "CON3") (pin "6") (pinfunction "6_6") (pintype "passive"))
      (node (ref "CON4") (pin "45") (pinfunction "45_45") (pintype "passive"))
      (node (ref "IC1") (pin "10") (pinfunction "SCL_10") (pintype "input"))
      (node (ref "IC1") (pin "16") (pinfunction "VCC_16") (pintype "power_in"))
      (node (ref "IC10") (pin "10") (pinfunction "SCL_10") (pintype "input"))
      (node (ref "IC10") (pin "16") (pinfunction "VCC_16") (pintype "power_in"))
      (node (ref "IC11") (pin "10") (pinfunction "SCL_10") (pintype "input"))
      (node (ref "IC11") (pin "16") (pinfunction "VCC_16") (pintype "power_in"))
      (node (ref "IC12") (pin "10") (pinfunction "SCL_10") (pintype "input"))
      (node (ref "IC12") (pin "16") (pinfunction "VCC_16") (pintype "power_in"))
      (node (ref "IC13") (pin "14") (pinfunction "VCC_14") (pintype "power_in"))
      (node (ref "IC14") (pin "14") (pinfunction "VCC_14") (pintype "power_in"))
      (node (ref "IC15") (pin "14") (pinfunction "VCC_14") (pintype "power_in"))
      (node (ref "IC16") (pin "16") (pinfunction "VCC_16") (pintype "power_in"))
      (node (ref "IC17") (pin "16") (pinfunction "VCC_16") (pintype "power_in"))
      (node (ref "IC18") (pin "14") (pinfunction "VCC_14") (pintype "power_in"))
      (node (ref "IC20") (pin "3") (pinfunction "VO_3") (pintype "passive"))
      (node (ref "IC21") (pin "16") (pinfunction "VCC_16") (pintype "power_in"))
      (node (ref "IC22") (pin "8") (pinfunction "VCC_8") (pintype "power_in"))
      (node (ref "IC4") (pin "10") (pinfunction "SCL_10") (pintype "input"))
      (node (ref "IC4") (pin "16") (pinfunction "VCC_16") (pintype "power_in"))
      (node (ref "IC5") (pin "10") (pinfunction "SCL_10") (pintype "input"))
      (node (ref "IC5") (pin "16") (pinfunction "VCC_16") (pintype "power_in"))
      (node (ref "LED1") (pin "2") (pinfunction "A_2") (pintype "bidirectional"))
      (node (ref "U$1") (pin "P$18") (pinfunction "5V_P$18") (pintype "bidirectional"))
    )
    (net (code "175") (name "VCC{slash}2") (class "Default")
      (node (ref "C9") (pin "+") (pinfunction "+_+") (pintype "passive"))
      (node (ref "CON4") (pin "42") (pinfunction "42_42") (pintype "passive"))
      (node (ref "CON4") (pin "43") (pinfunction "43_43") (pintype "passive"))
      (node (ref "D3") (pin "C") (pinfunction "C_C") (pintype "passive"))
      (node (ref "D4") (pin "C") (pinfunction "C_C") (pintype "passive"))
      (node (ref "IC19") (pin "1") (pinfunction "VIN_1") (pintype "power_in"))
      (node (ref "Q1") (pin "C") (pinfunction "C_C") (pintype "passive"))
      (node (ref "R4") (pin "2") (pinfunction "2_2") (pintype "passive"))
    )
    (net (code "176") (name "V_PP") (class "Default")
      (node (ref "CON3") (pin "1") (pinfunction "1_1") (pintype "passive"))
      (node (ref "CON3") (pin "2") (pinfunction "2_2") (pintype "passive"))
      (node (ref "CON4") (pin "44") (pinfunction "44_44") (pintype "passive"))
      (node (ref "D3") (pin "A") (pinfunction "A_A") (pintype "passive"))
      (node (ref "IC2") (pin "10") (pinfunction "CD+_10") (pintype "passive"))
      (node (ref "IC3") (pin "9") (pinfunction "VS_9") (pintype "passive"))
      (node (ref "IC6") (pin "10") (pinfunction "CD+_10") (pintype "passive"))
      (node (ref "IC7") (pin "10") (pinfunction "CD+_10") (pintype "passive"))
      (node (ref "IC8") (pin "9") (pinfunction "VS_9") (pintype "passive"))
      (node (ref "IC9") (pin "9") (pinfunction "VS_9") (pintype "passive"))
      (node (ref "R6") (pin "1") (pinfunction "1_1") (pintype "passive"))
      (node (ref "T2") (pin "2") (pinfunction "E_2") (pintype "passive"))
    )
    (net (code "177") (name "ZEILEN_CLK") (class "Default")
      (node (ref "IC1") (pin "11") (pinfunction "SCK_11") (pintype "input"))
      (node (ref "IC10") (pin "11") (pinfunction "SCK_11") (pintype "input"))
      (node (ref "IC11") (pin "11") (pinfunction "SCK_11") (pintype "input"))
      (node (ref "IC12") (pin "11") (pinfunction "SCK_11") (pintype "input"))
      (node (ref "IC4") (pin "11") (pinfunction "SCK_11") (pintype "input"))
      (node (ref "IC5") (pin "11") (pinfunction "SCK_11") (pintype "input"))
      (node (ref "U$1") (pin "P$31") (pinfunction "PA5_P$31") (pintype "bidirectional"))
    )
    (net (code "178") (name "ZEILEN_D") (class "Default")
      (node (ref "IC1") (pin "14") (pinfunction "SER_14") (pintype "input"))
      (node (ref "IC10") (pin "14") (pinfunction "SER_14") (pintype "input"))
      (node (ref "U$1") (pin "P$29") (pinfunction "PA7_P$29") (pintype "bidirectional"))
    )
    (net (code "179") (name "ZEILEN_LATCH") (class "Default")
      (node (ref "IC1") (pin "12") (pinfunction "RCK_12") (pintype "input"))
      (node (ref "IC10") (pin "12") (pinfunction "RCK_12") (pintype "input"))
      (node (ref "IC11") (pin "12") (pinfunction "RCK_12") (pintype "input"))
      (node (ref "IC12") (pin "12") (pinfunction "RCK_12") (pintype "input"))
      (node (ref "IC4") (pin "12") (pinfunction "RCK_12") (pintype "input"))
      (node (ref "IC5") (pin "12") (pinfunction "RCK_12") (pintype "input"))
      (node (ref "U$1") (pin "P$30") (pinfunction "PA6_P$30") (pintype "bidirectional"))
    )
    (net (code "180") (name "ZEILEN_OE") (class "Default")
      (node (ref "IC13") (pin "10") (pinfunction "I1_10") (pintype "input"))
      (node (ref "IC13") (pin "5") (pinfunction "I1_5") (pintype "input"))
      (node (ref "R13") (pin "2") (pinfunction "2_2") (pintype "passive"))
      (node (ref "U$1") (pin "P$32") (pinfunction "PA4_P$32") (pintype "bidirectional"))
    )
    (net (code "181") (name "unconnected-(CON4-Pad46)") (class "Default")
      (node (ref "CON4") (pin "46") (pinfunction "46_46") (pintype "passive"))
    )
    (net (code "182") (name "unconnected-(CON4-Pad61)") (class "Default")
      (node (ref "CON4") (pin "61") (pinfunction "61_61") (pintype "passive"))
    )
    (net (code "183") (name "unconnected-(CON4-Pad62)") (class "Default")
      (node (ref "CON4") (pin "62") (pinfunction "62_62") (pintype "passive"))
    )
    (net (code "184") (name "unconnected-(CON4-Pad63)") (class "Default")
      (node (ref "CON4") (pin "63") (pinfunction "63_63") (pintype "passive"))
    )
    (net (code "185") (name "unconnected-(CON4-Pad64)") (class "Default")
      (node (ref "CON4") (pin "64") (pinfunction "64_64") (pintype "passive"))
    )
    (net (code "186") (name "unconnected-(IC5A-QH*-Pad9)") (class "Default")
      (node (ref "IC5") (pin "9") (pinfunction "QH*_9") (pintype "tri_state"))
    )
    (net (code "187") (name "unconnected-(IC7-O5-Pad14)") (class "Default")
      (node (ref "IC7") (pin "14") (pinfunction "O5_14") (pintype "open_collector"))
    )
    (net (code "188") (name "unconnected-(IC7-O6-Pad13)") (class "Default")
      (node (ref "IC7") (pin "13") (pinfunction "O6_13") (pintype "open_collector"))
    )
    (net (code "189") (name "unconnected-(IC7-O7-Pad12)") (class "Default")
      (node (ref "IC7") (pin "12") (pinfunction "O7_12") (pintype "open_collector"))
    )
    (net (code "190") (name "unconnected-(IC7-O8-Pad11)") (class "Default")
      (node (ref "IC7") (pin "11") (pinfunction "O8_11") (pintype "open_collector"))
    )
    (net (code "191") (name "unconnected-(IC9-O5-Pad14)") (class "Default")
      (node (ref "IC9") (pin "14") (pinfunction "O5_14") (pintype "open_collector"))
    )
    (net (code "192") (name "unconnected-(IC9-O6-Pad13)") (class "Default")
      (node (ref "IC9") (pin "13") (pinfunction "O6_13") (pintype "open_collector"))
    )
    (net (code "193") (name "unconnected-(IC9-O7-Pad12)") (class "Default")
      (node (ref "IC9") (pin "12") (pinfunction "O7_12") (pintype "open_collector"))
    )
    (net (code "194") (name "unconnected-(IC9-O8-Pad11)") (class "Default")
      (node (ref "IC9") (pin "11") (pinfunction "O8_11") (pintype "open_collector"))
    )
    (net (code "195") (name "unconnected-(IC12A-QH*-Pad9)") (class "Default")
      (node (ref "IC12") (pin "9") (pinfunction "QH*_9") (pintype "tri_state"))
    )
    (net (code "196") (name "unconnected-(IC17A-QG-Pad6)") (class "Default")
      (node (ref "IC17") (pin "6") (pinfunction "QG_6") (pintype "tri_state"))
    )
    (net (code "197") (name "unconnected-(IC17A-QH*-Pad9)") (class "Default")
      (node (ref "IC17") (pin "9") (pinfunction "QH*_9") (pintype "tri_state"))
    )
    (net (code "198") (name "unconnected-(IC17A-QH-Pad7)") (class "Default")
      (node (ref "IC17") (pin "7") (pinfunction "QH_7") (pintype "tri_state"))
    )
    (net (code "199") (name "unconnected-(IC21A-R2IN-Pad8)") (class "Default")
      (node (ref "IC21") (pin "8") (pinfunction "R2IN_8") (pintype "input"))
    )
    (net (code "200") (name "unconnected-(IC21A-R2OUT-Pad9)") (class "Default")
      (node (ref "IC21") (pin "9") (pinfunction "R2OUT_9") (pintype "output"))
    )
    (net (code "201") (name "unconnected-(IC21A-T2IN-Pad10)") (class "Default")
      (node (ref "IC21") (pin "10") (pinfunction "T2IN_10") (pintype "input"))
    )
    (net (code "202") (name "unconnected-(IC21A-T2OUT-Pad7)") (class "Default")
      (node (ref "IC21") (pin "7") (pinfunction "T2OUT_7") (pintype "output"))
    )
    (net (code "203") (name "unconnected-(U$1-3.3V1-PadP$20)") (class "Default")
      (node (ref "U$1") (pin "P$20") (pinfunction "3.3V1_P$20") (pintype "bidirectional"))
    )
    (net (code "204") (name "unconnected-(U$1-PA0-PadP$36)") (class "Default")
      (node (ref "U$1") (pin "P$36") (pinfunction "PA0_P$36") (pintype "bidirectional"))
    )
    (net (code "205") (name "unconnected-(U$1-PA11-PadP$8)") (class "Default")
      (node (ref "U$1") (pin "P$8") (pinfunction "PA11_P$8") (pintype "bidirectional"))
    )
    (net (code "206") (name "unconnected-(U$1-PA12-PadP$9)") (class "Default")
      (node (ref "U$1") (pin "P$9") (pinfunction "PA12_P$9") (pintype "bidirectional"))
    )
    (net (code "207") (name "unconnected-(U$1-PA15-PadP$10)") (class "Default")
      (node (ref "U$1") (pin "P$10") (pinfunction "PA15_P$10") (pintype "bidirectional"))
    )
    (net (code "208") (name "unconnected-(U$1-PB9-PadP$17)") (class "Default")
      (node (ref "U$1") (pin "P$17") (pinfunction "PB9_P$17") (pintype "bidirectional"))
    )
    (net (code "209") (name "unconnected-(U$1-PC13-PadP$39)") (class "Default")
      (node (ref "U$1") (pin "P$39") (pinfunction "PC13_P$39") (pintype "bidirectional"))
    )
    (net (code "210") (name "unconnected-(U$1-PC14-PadP$38)") (class "Default")
      (node (ref "U$1") (pin "P$38") (pinfunction "PC14_P$38") (pintype "bidirectional"))
    )
    (net (code "211") (name "unconnected-(U$1-PC15-PadP$37)") (class "Default")
      (node (ref "U$1") (pin "P$37") (pinfunction "PC15_P$37") (pintype "bidirectional"))
    )
    (net (code "212") (name "unconnected-(U$1-VBAT-PadP$40)") (class "Default")
      (node (ref "U$1") (pin "P$40") (pinfunction "VBAT_P$40") (pintype "bidirectional"))
    )
  )
)
